# Sheet1.net
KiCad netlist of a schematic drawn in Altium Designer
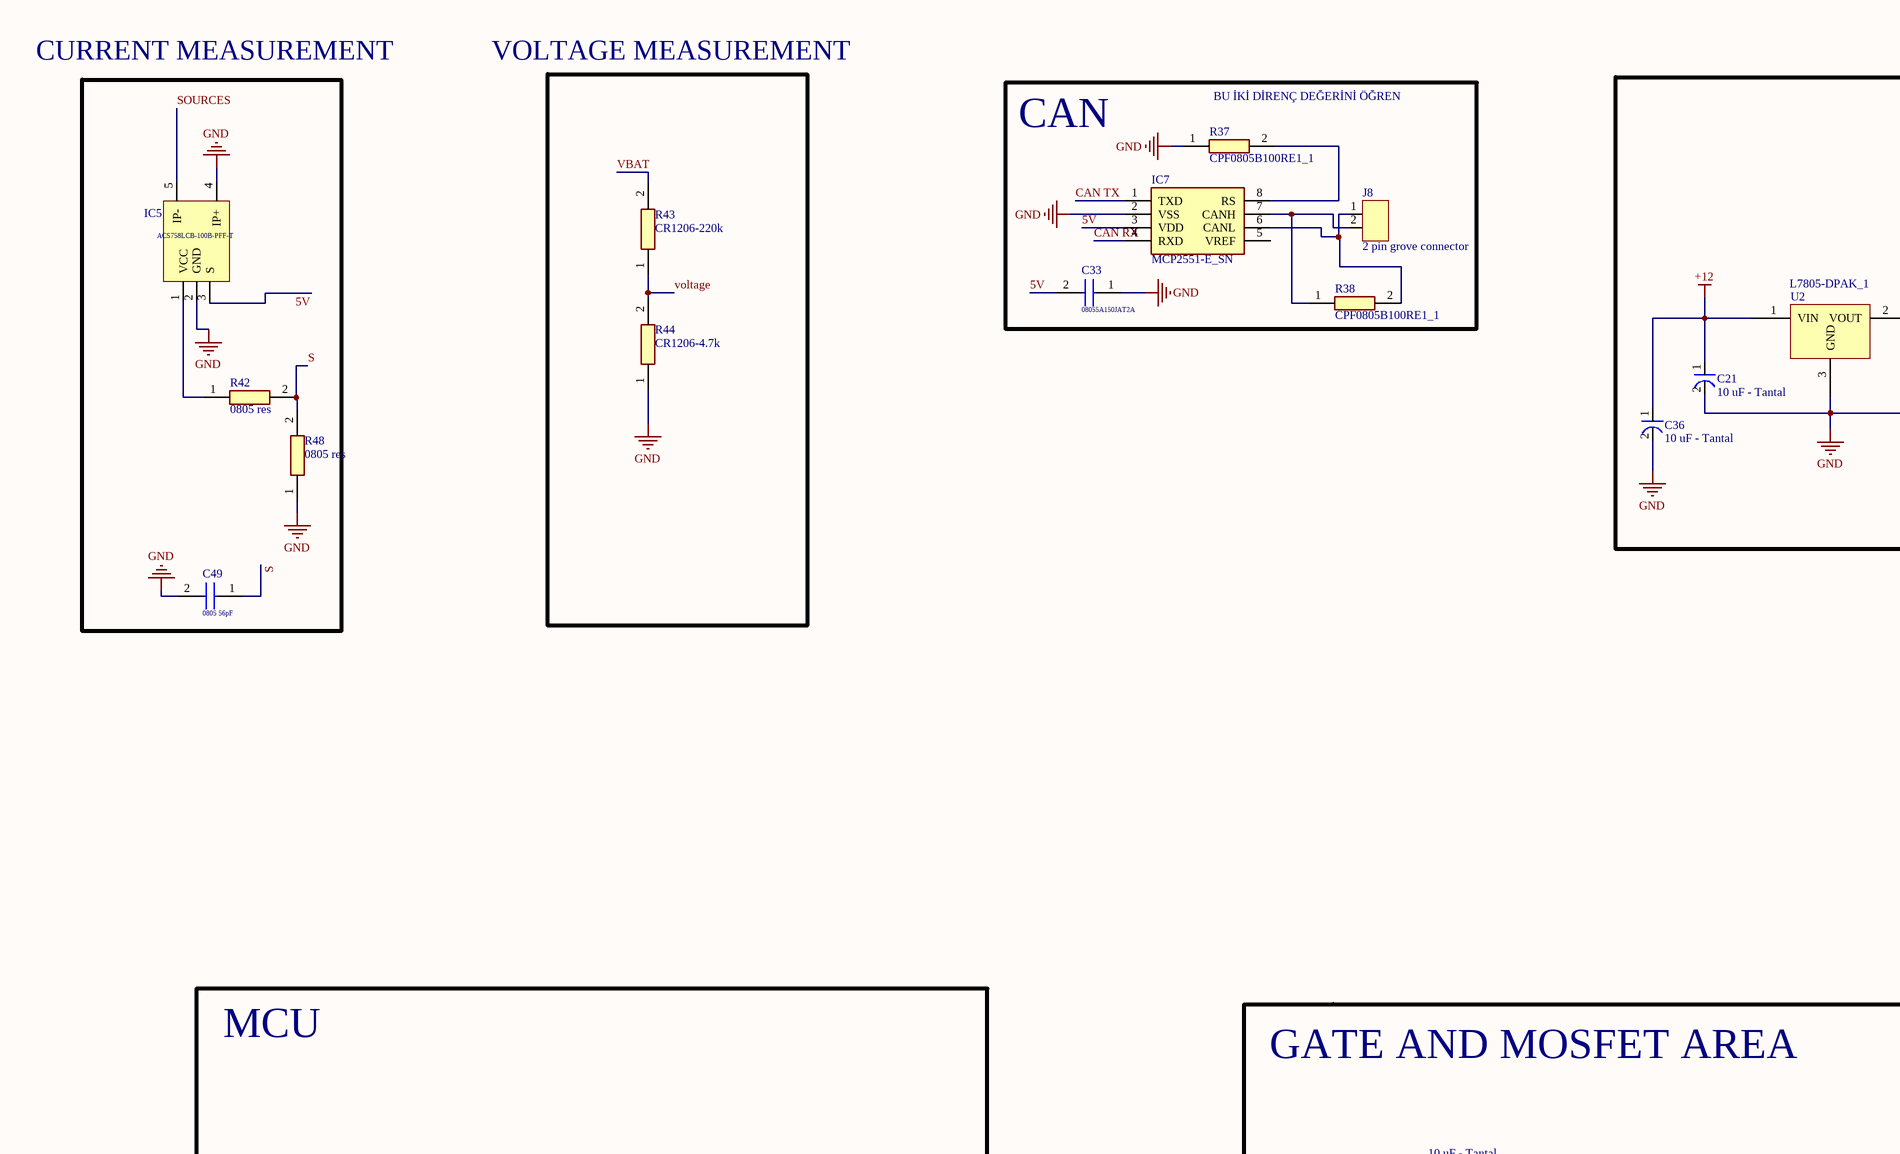
[diagram p0: Sheet1.SchDoc, top left]
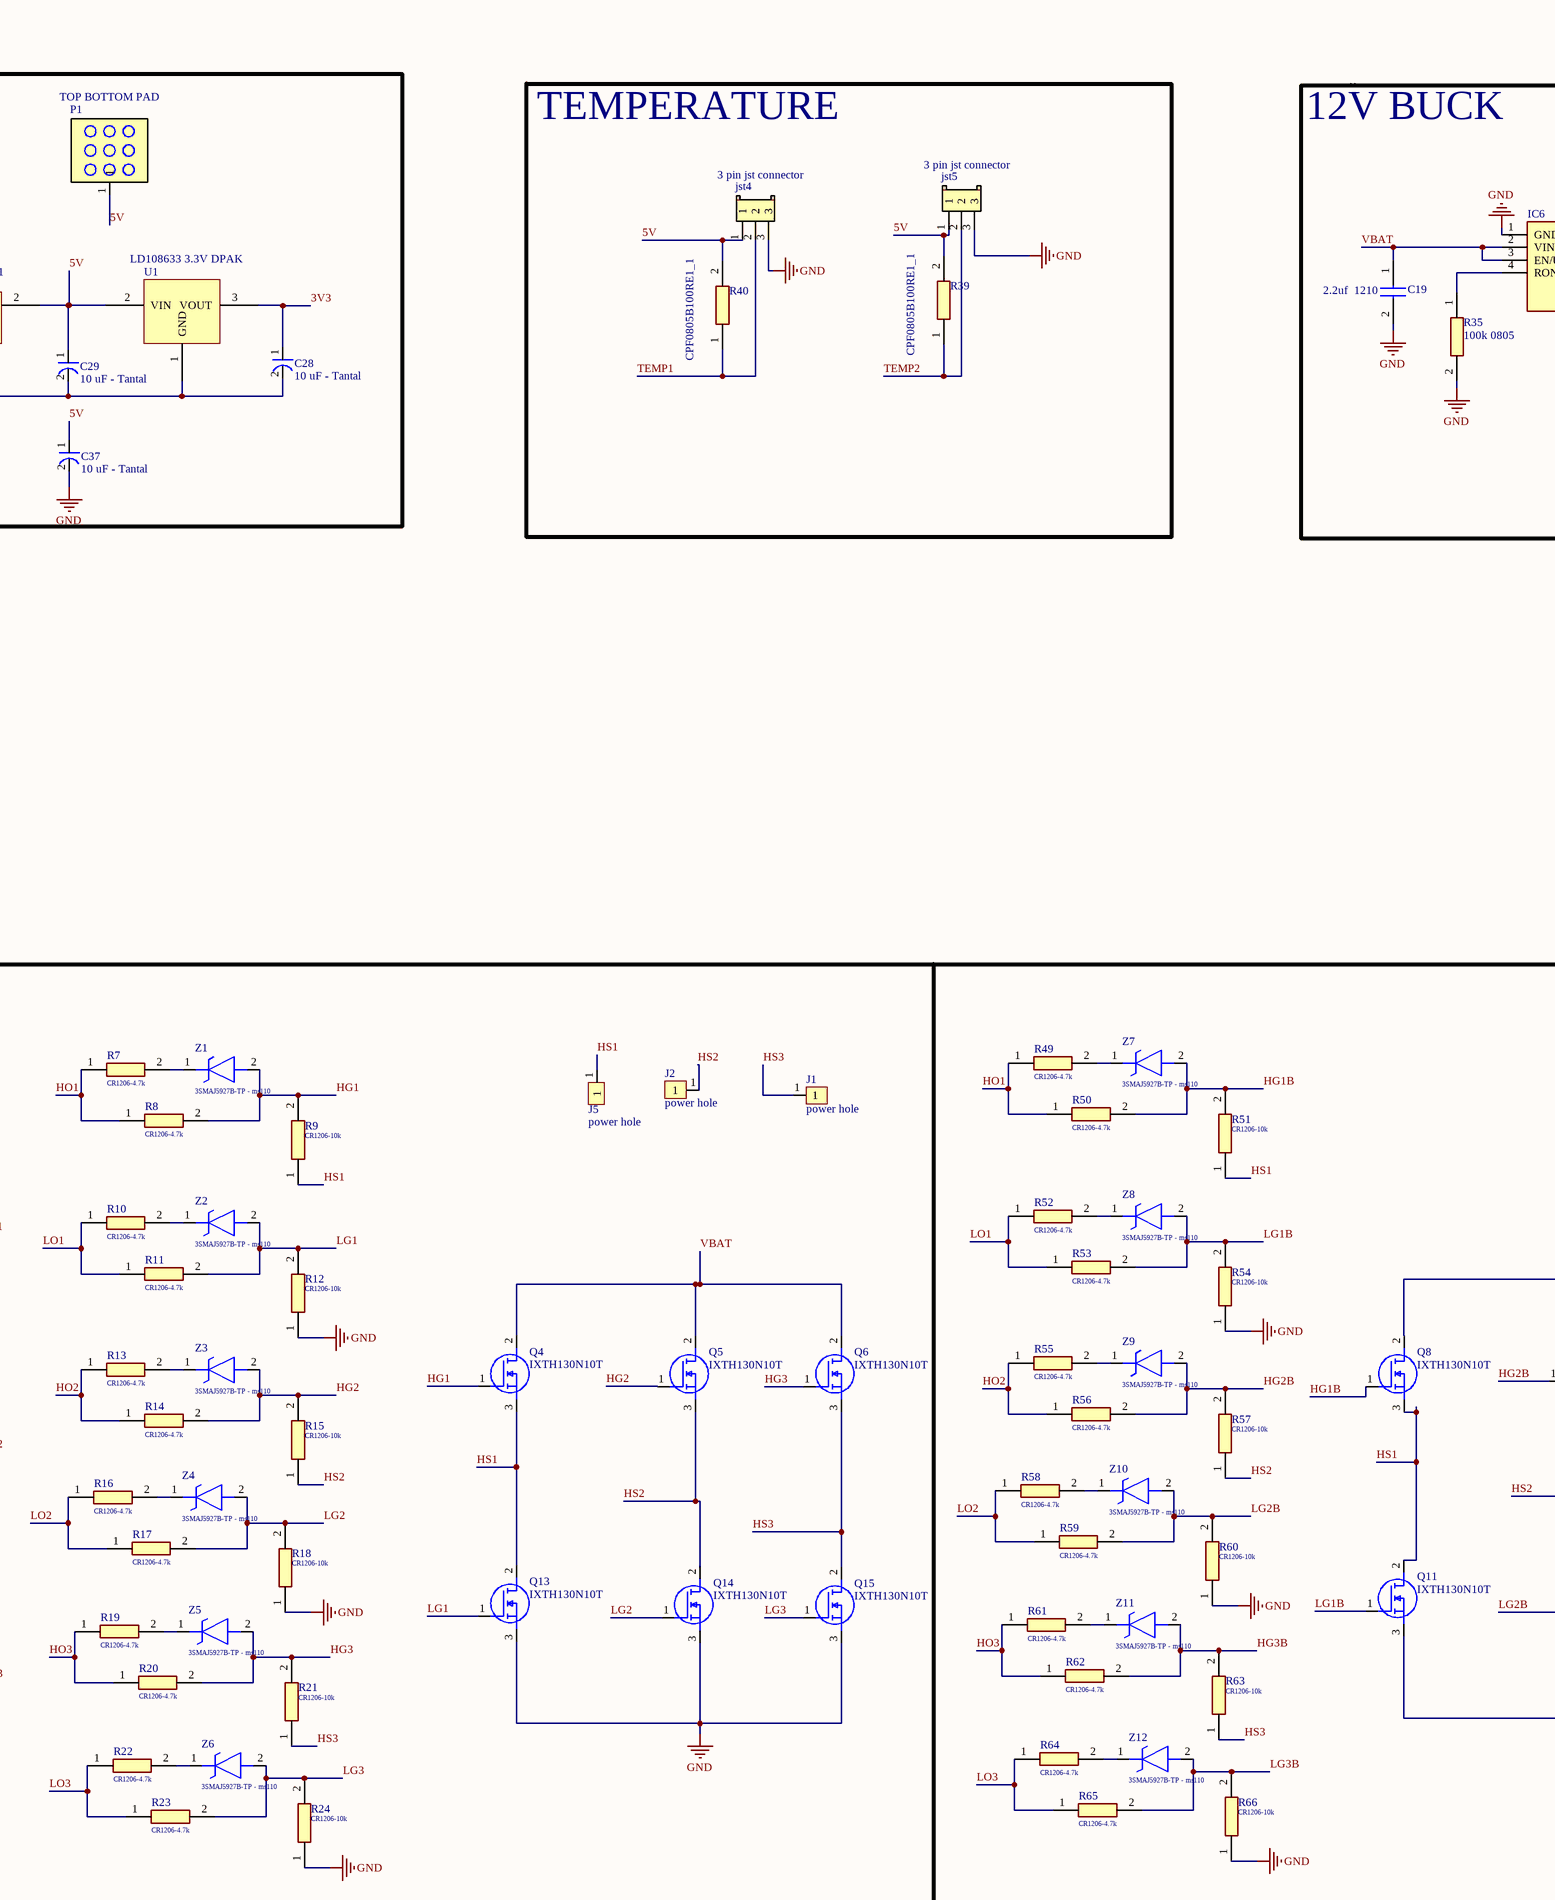
[diagram p1: Sheet1.SchDoc, top middle]
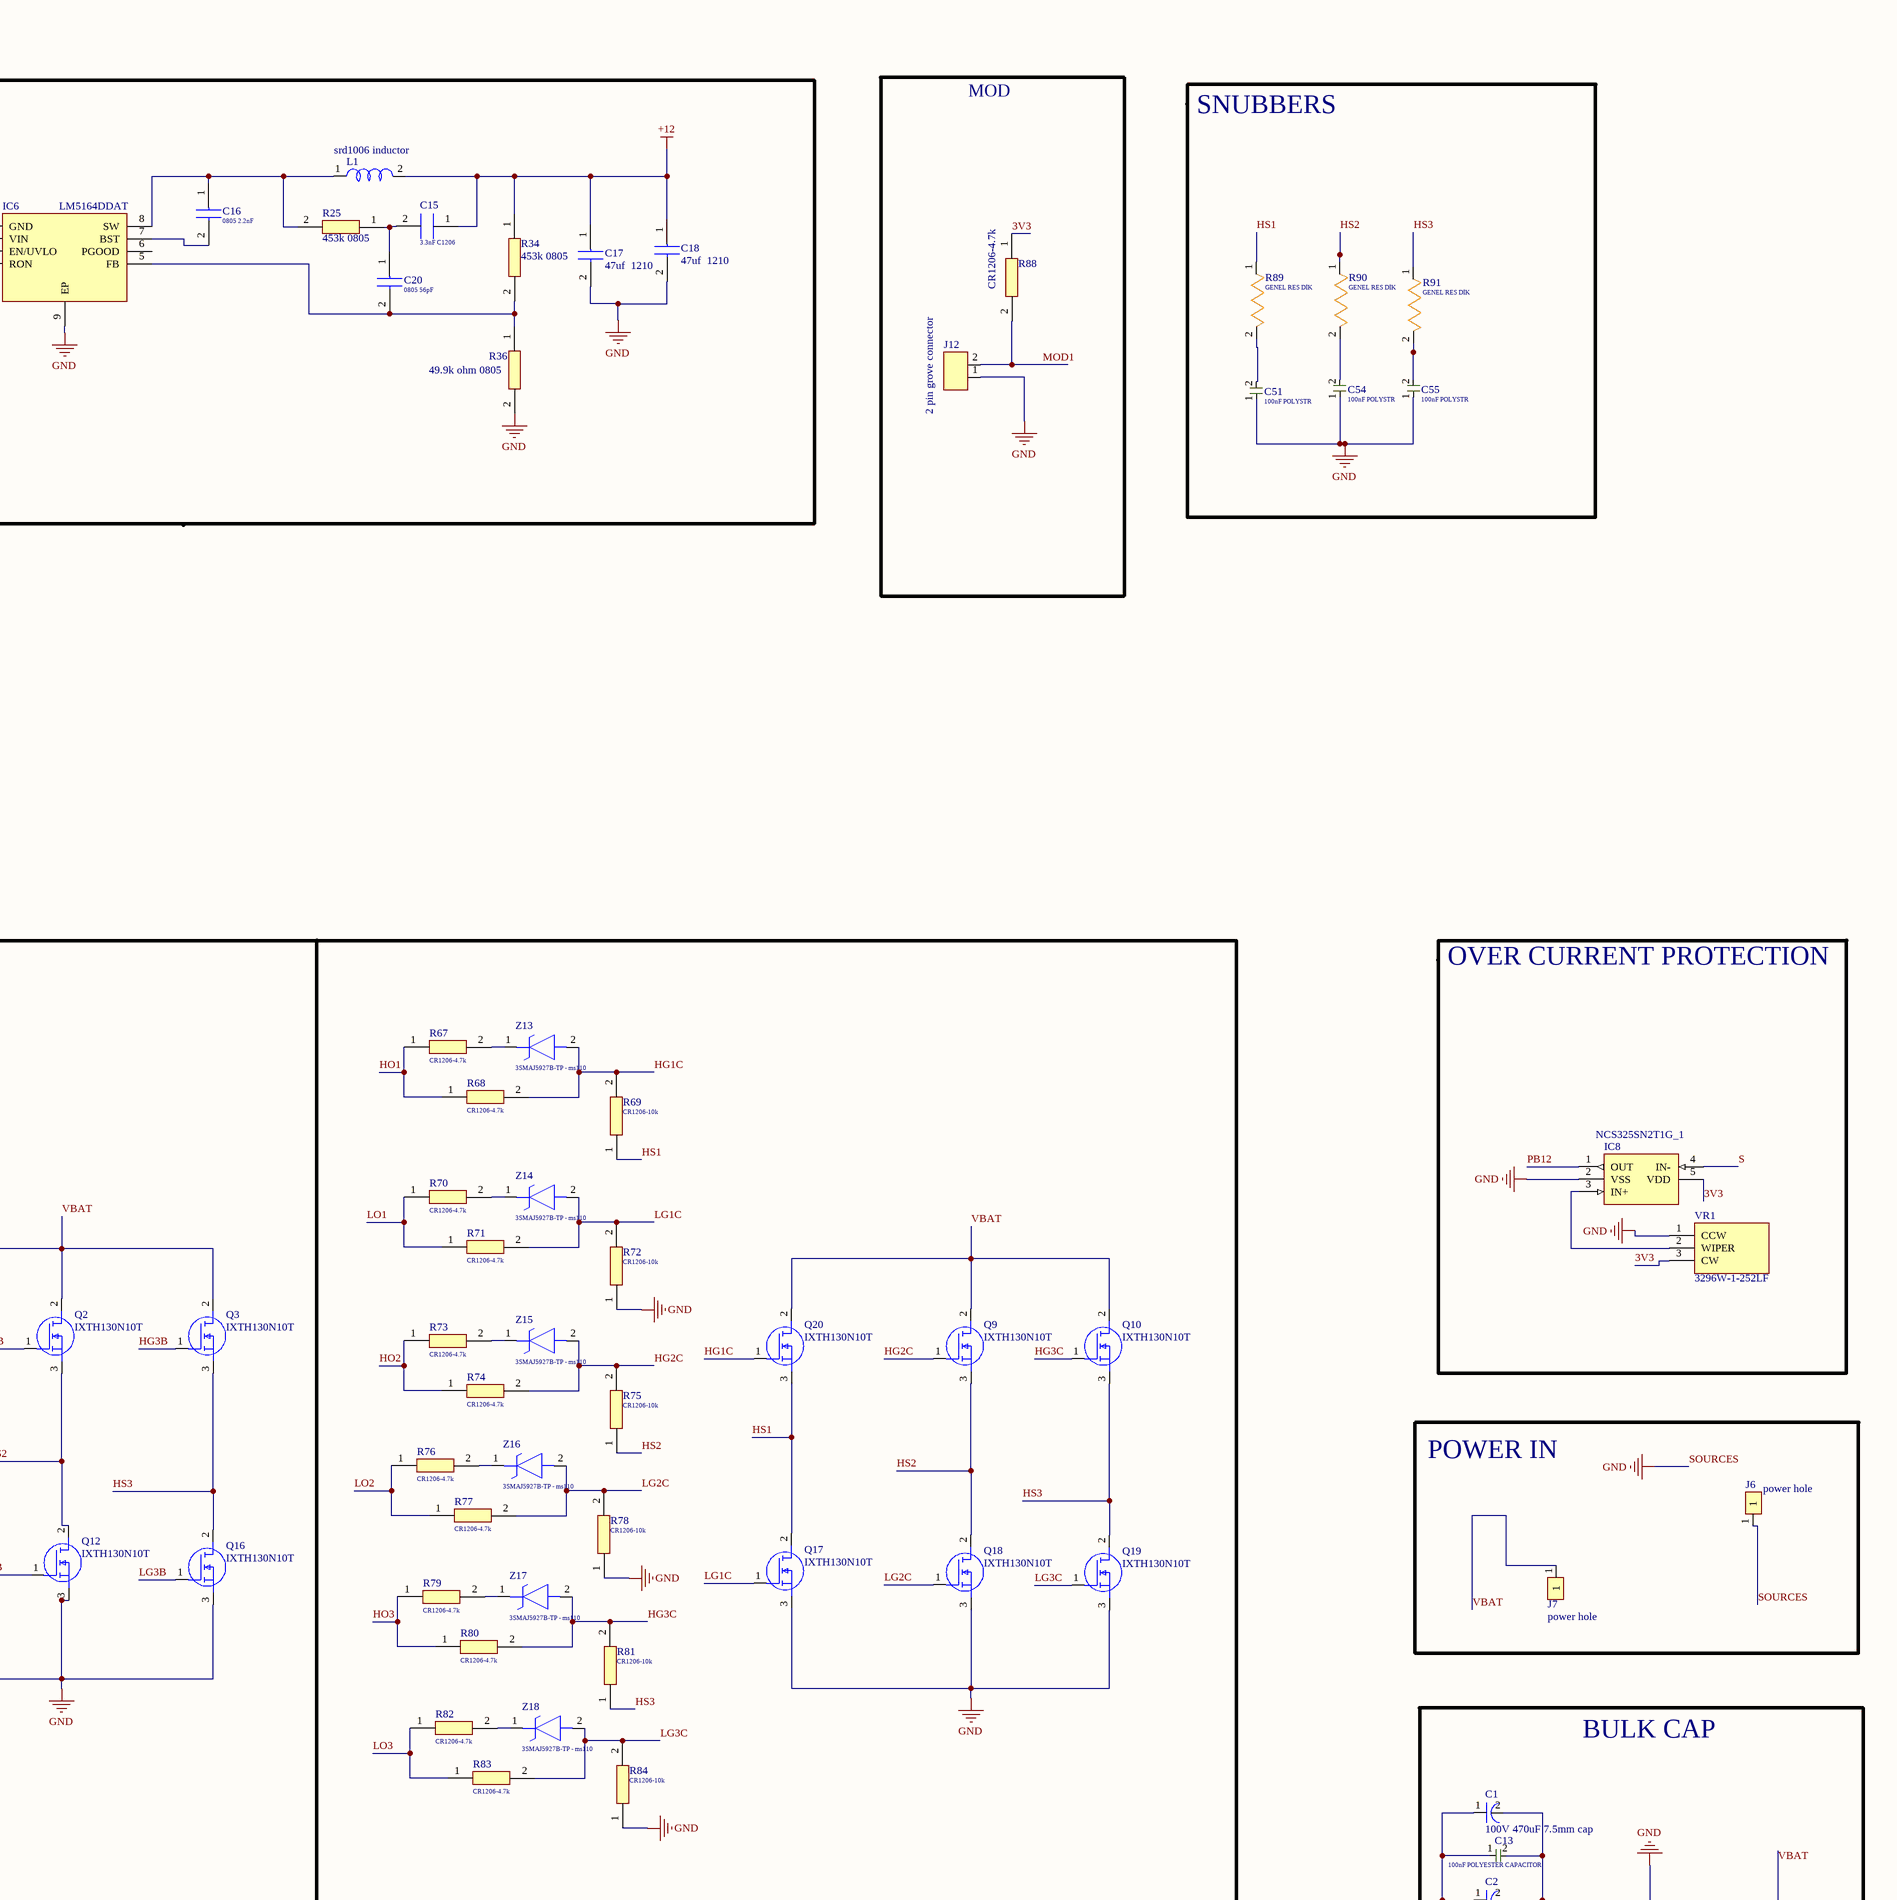
[diagram p2: Sheet1.SchDoc, top right]
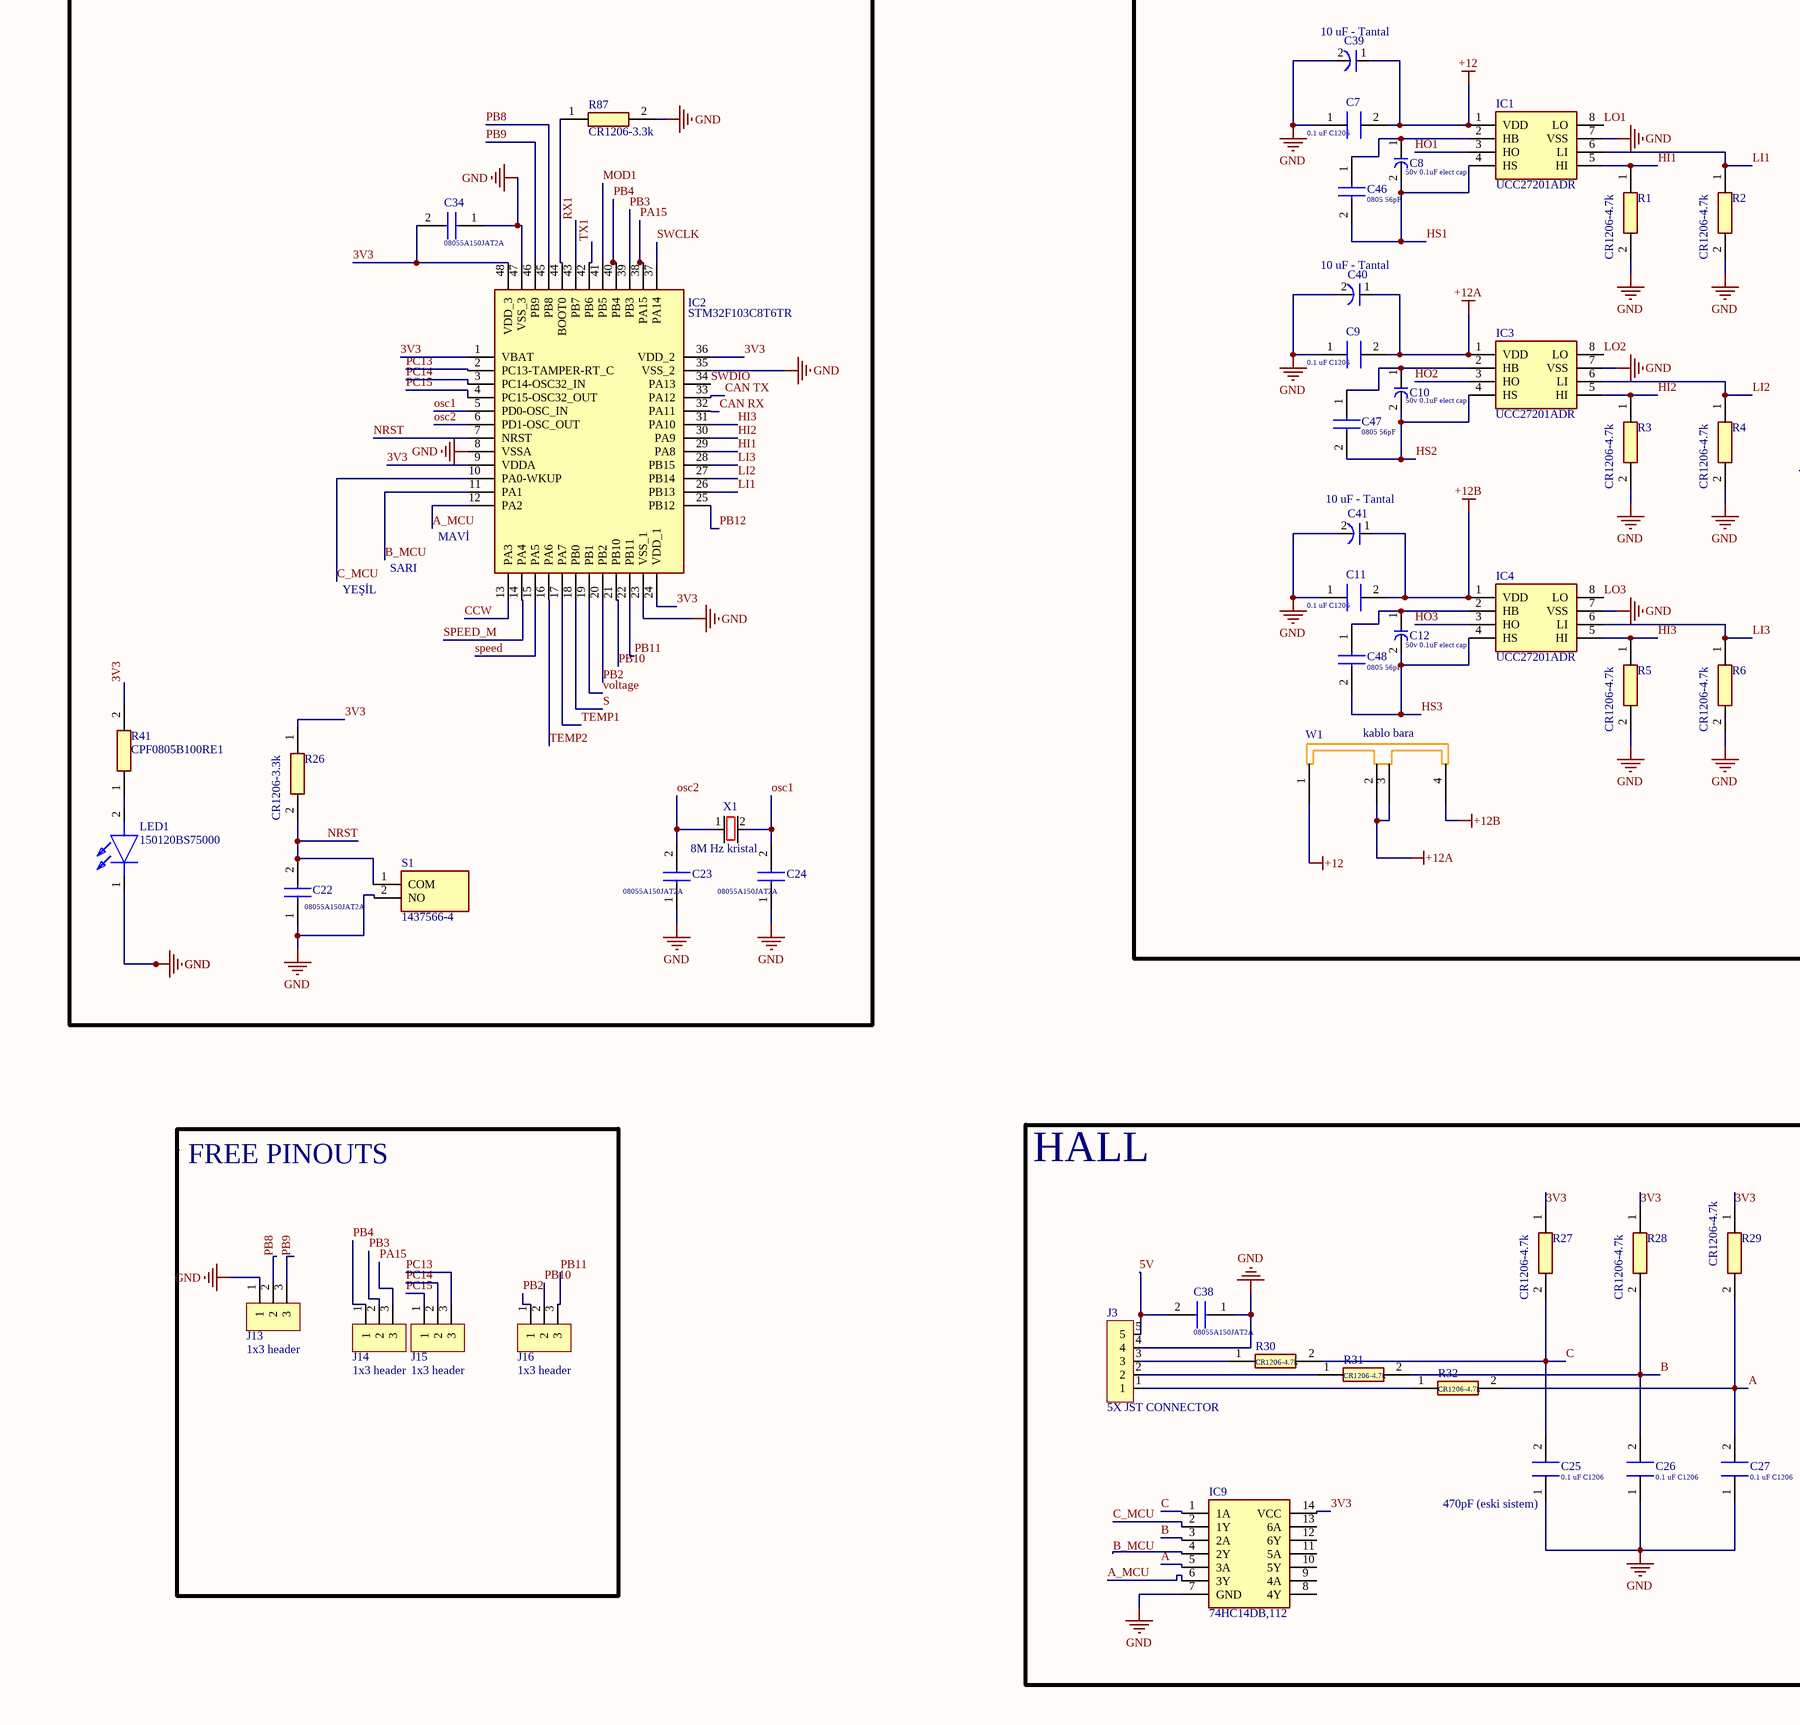
[diagram p3: Sheet1.SchDoc, bottom left]
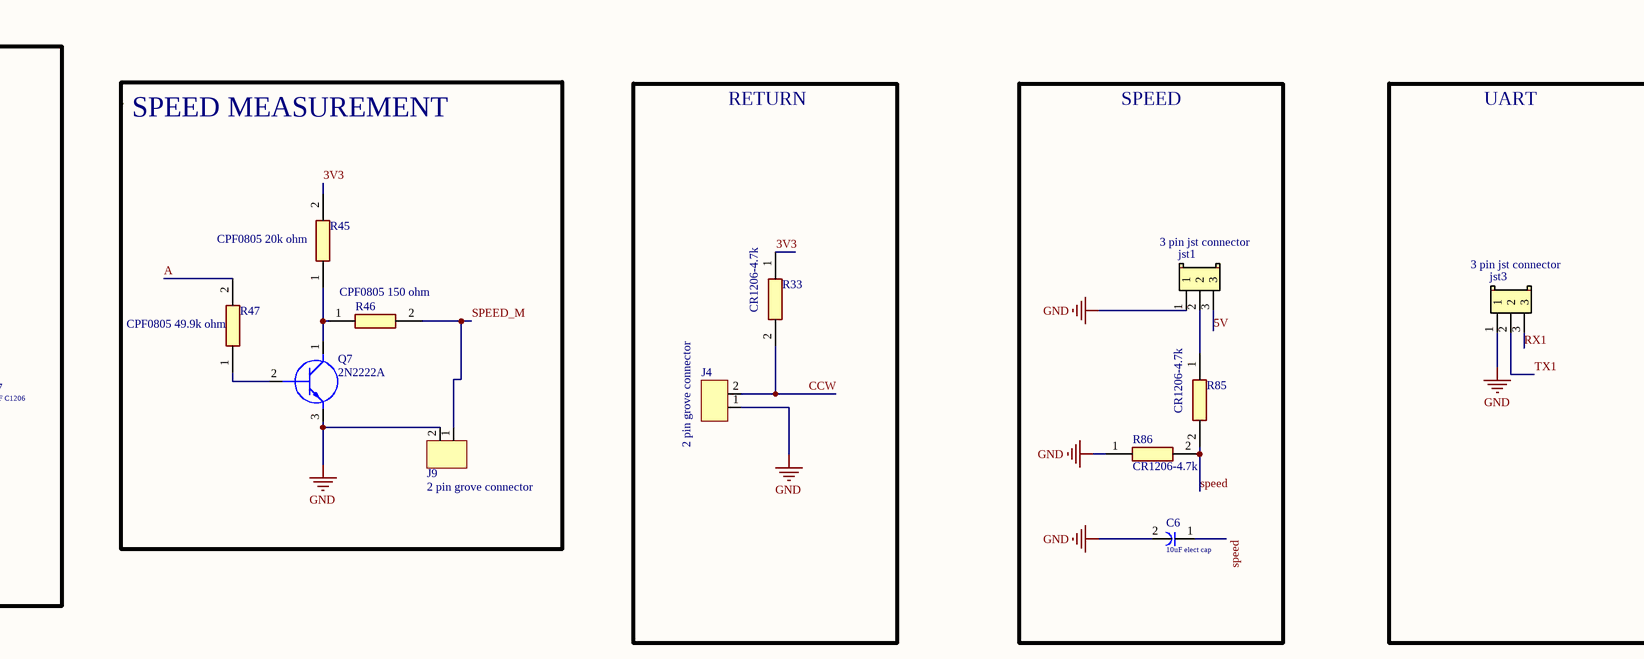
[diagram p4: Sheet1.SchDoc, bottom middle]
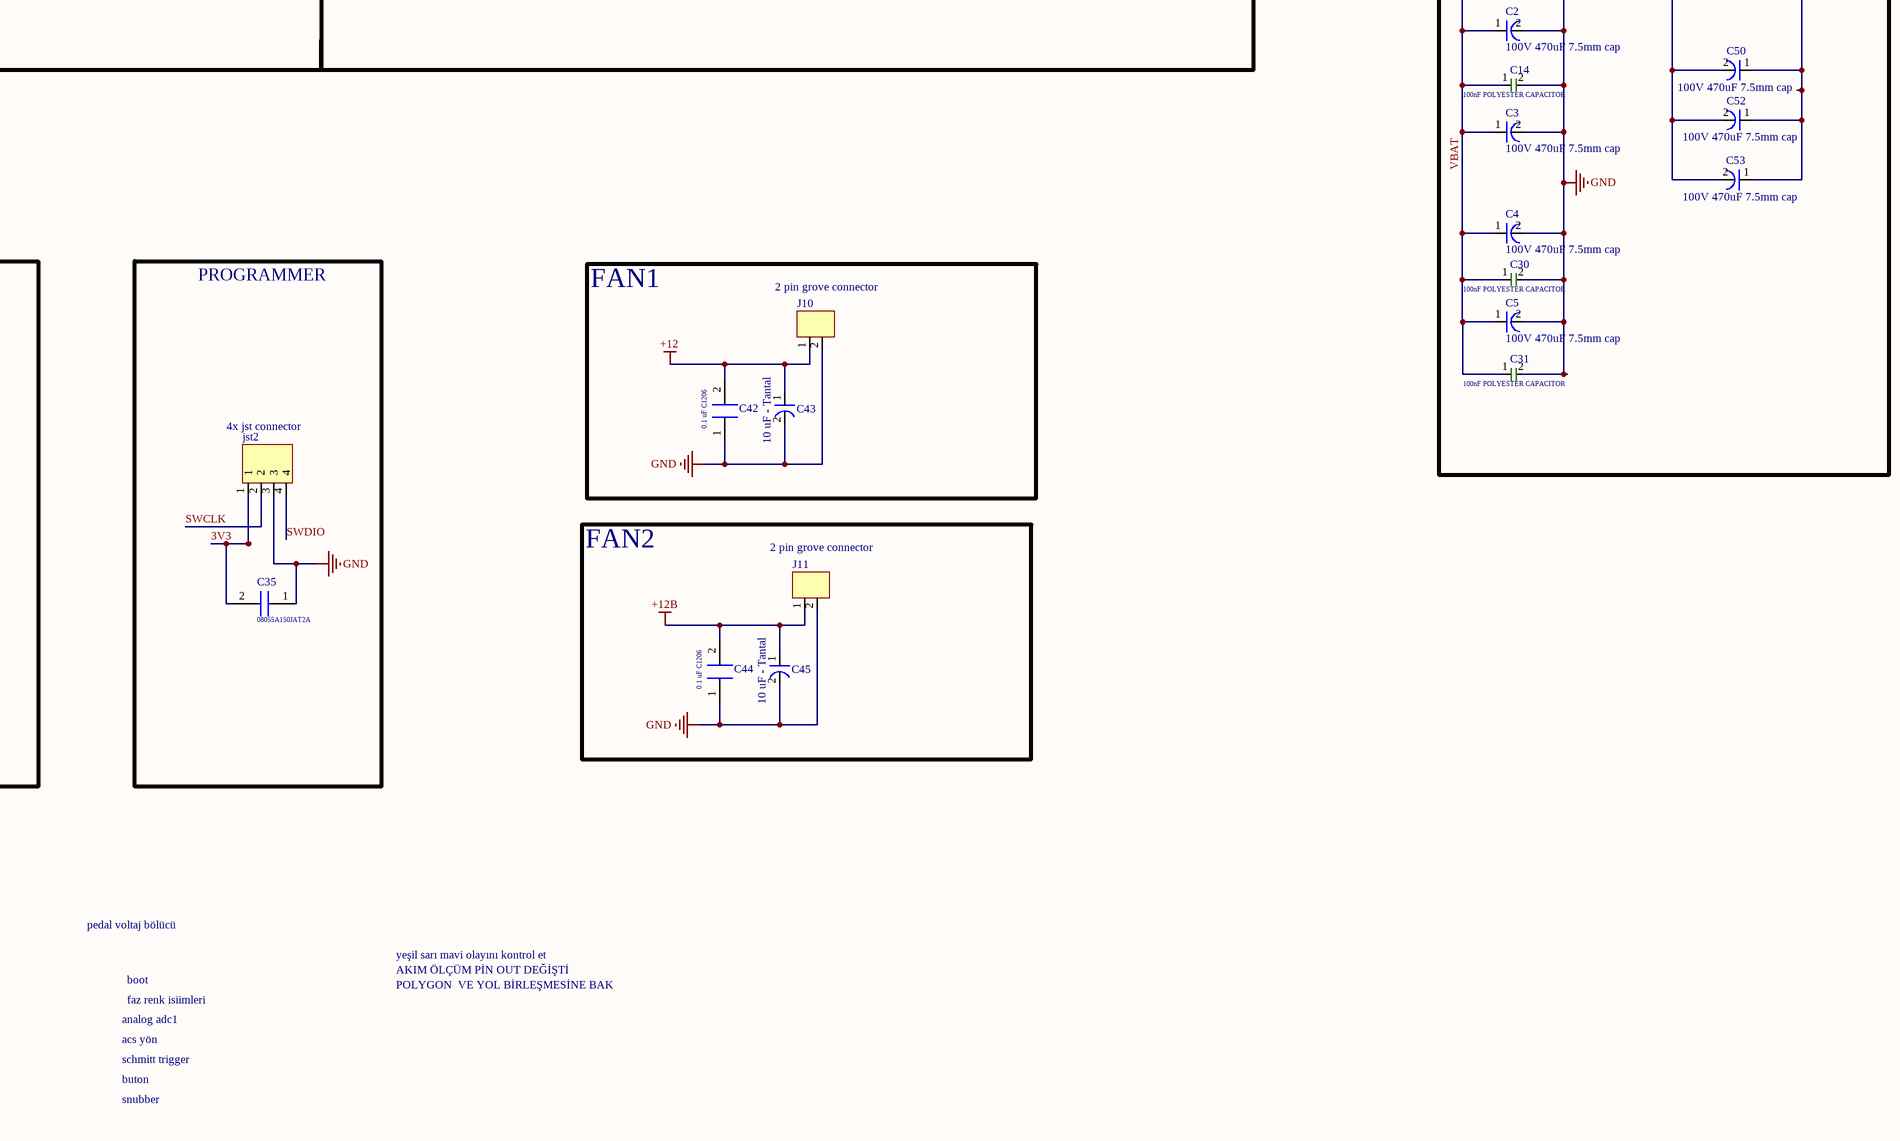
[diagram p5: Sheet1.SchDoc, bottom right]

(export (version "E")
  (design (tool "Eeschema 10.0.6"))
  (components
    (comp (ref "C1")
      (value "100V 470uF 7.5mm cap")
      (footprint "100v 470UF")
      (description "bulk")
      (libsource (lib "Schlib1") (part "100V 470uF 7.5mm cap"))
    )
    (comp (ref "C2")
      (value "100V 470uF 7.5mm cap")
      (footprint "100v 470UF")
      (description "bulk")
      (libsource (lib "Schlib1") (part "100V 470uF 7.5mm cap"))
    )
    (comp (ref "C3")
      (value "100V 470uF 7.5mm cap")
      (footprint "100v 470UF")
      (description "bulk")
      (libsource (lib "Schlib1") (part "100V 470uF 7.5mm cap"))
    )
    (comp (ref "C4")
      (value "100V 470uF 7.5mm cap")
      (footprint "100v 470UF")
      (description "bulk")
      (libsource (lib "Schlib1") (part "100V 470uF 7.5mm cap"))
    )
    (comp (ref "C5")
      (value "100V 470uF 7.5mm cap")
      (footprint "100v 470UF")
      (description "bulk")
      (libsource (lib "Schlib1") (part "100V 470uF 7.5mm cap"))
    )
    (comp (ref "C6")
      (value "10uF elect cap")
      (footprint "50V 0.1uF elect cap")
      (libsource (lib "Schlib1") (part "50v 0.1uF elect cap"))
    )
    (comp (ref "C7")
      (value "0.1 uF C1206")
      (footprint "C1206")
      (libsource (lib "Schlib1") (part "0.1 uF C1206"))
    )
    (comp (ref "C8")
      (value "50v 0.1uF elect cap")
      (footprint "50V 0.1uF elect cap")
      (libsource (lib "Schlib1") (part "50v 0.1uF elect cap"))
    )
    (comp (ref "C9")
      (value "0.1 uF C1206")
      (footprint "C1206")
      (libsource (lib "Schlib1") (part "0.1 uF C1206"))
    )
    (comp (ref "C10")
      (value "50v 0.1uF elect cap")
      (footprint "50V 0.1uF elect cap")
      (libsource (lib "Schlib1") (part "50v 0.1uF elect cap"))
    )
    (comp (ref "C11")
      (value "0.1 uF C1206")
      (footprint "C1206")
      (libsource (lib "Schlib1") (part "0.1 uF C1206"))
    )
    (comp (ref "C12")
      (value "50v 0.1uF elect cap")
      (footprint "50V 0.1uF elect cap")
      (libsource (lib "Schlib1") (part "50v 0.1uF elect cap"))
    )
    (comp (ref "C13")
      (value "100nF POLYESTER CAPACITOR")
      (footprint "100uF POLYESTER CAPACITOR")
      (libsource (lib "Schlib1") (part "100nF POLYESTER CAPACITOR"))
    )
    (comp (ref "C14")
      (value "100nF POLYESTER CAPACITOR")
      (footprint "100uF POLYESTER CAPACITOR")
      (libsource (lib "Schlib1") (part "100nF POLYESTER CAPACITOR"))
    )
    (comp (ref "C15")
      (value "3.3nF C1206")
      (footprint "C1206")
      (description "0.1 uF C1206")
      (libsource (lib "Schlib1") (part "0.1 uF C1206"))
    )
    (comp (ref "C16")
      (value "0805 2.2nF")
      (footprint "PcbLib1:CAPC2012X94N")
      (description "Capacitor")
      (fields
        (field (name "MANUFACTURER_PART_NUMBER") "08055A150JAT2A")
        (field (name "MOUSER PART NUMBER") "581-08055A150J")
      )
      (libsource (lib "Schlib1") (part "08055A150JAT2A"))
    )
    (comp (ref "C17")
      (value "47uf  1210")
      (footprint "PcbLib1:CAPC3225X270N")
      (description "Capacitor")
      (fields
        (field (name "MANUFACTURER_PART_NUMBER") "GRM32EC81C476KE15K")
        (field (name "MOUSER PART NUMBER") "81-GRM32EC81C476KE5K")
      )
      (libsource (lib "*") (part "GRM32EC81C476KE15K"))
    )
    (comp (ref "C18")
      (value "47uf  1210")
      (footprint "PcbLib1:CAPC3225X270N")
      (description "Capacitor")
      (fields
        (field (name "MANUFACTURER_PART_NUMBER") "GRM32EC81C476KE15K")
        (field (name "MOUSER PART NUMBER") "81-GRM32EC81C476KE5K")
      )
      (libsource (lib "*") (part "GRM32EC81C476KE15K"))
    )
    (comp (ref "C19")
      (value "2.2uf  1210")
      (footprint "PcbLib1:CAPC3225X270N")
      (description "Capacitor")
      (fields
        (field (name "MANUFACTURER_PART_NUMBER") "GRM32EC81C476KE15K")
        (field (name "MOUSER PART NUMBER") "81-GRM32EC81C476KE5K")
      )
      (libsource (lib "*") (part "GRM32EC81C476KE15K"))
    )
    (comp (ref "C20")
      (value "0805 56pF")
      (footprint "PcbLib1:CAPC2012X94N")
      (description "Capacitor")
      (fields
        (field (name "MANUFACTURER_PART_NUMBER") "08055A150JAT2A")
        (field (name "MOUSER PART NUMBER") "581-08055A150J")
      )
      (libsource (lib "Schlib1") (part "08055A150JAT2A"))
    )
    (comp (ref "C21")
      (value "10 uF - Tantal")
      (footprint "C1206-TANT")
      (libsource (lib "Schlib1") (part "10 uF - Tantal"))
    )
    (comp (ref "C22")
      (value "08055A150JAT2A")
      (footprint "PcbLib1:CAPC2012X94N")
      (description "Capacitor")
      (fields (field (name "MOUSER PART NUMBER") "581-08055A150J"))
      (libsource (lib "Schlib1") (part "08055A150JAT2A"))
    )
    (comp (ref "C23")
      (value "08055A150JAT2A")
      (footprint "PcbLib1:CAPC2012X94N")
      (description "Capacitor")
      (fields (field (name "MOUSER PART NUMBER") "581-08055A150J"))
      (libsource (lib "Schlib1") (part "08055A150JAT2A"))
    )
    (comp (ref "C24")
      (value "08055A150JAT2A")
      (footprint "PcbLib1:CAPC2012X94N")
      (description "Capacitor")
      (fields (field (name "MOUSER PART NUMBER") "581-08055A150J"))
      (libsource (lib "Schlib1") (part "08055A150JAT2A"))
    )
    (comp (ref "C25")
      (value "0.1 uF C1206")
      (footprint "C1206")
      (libsource (lib "Schlib1") (part "0.1 uF C1206"))
    )
    (comp (ref "C26")
      (value "0.1 uF C1206")
      (footprint "C1206")
      (libsource (lib "Schlib1") (part "0.1 uF C1206"))
    )
    (comp (ref "C27")
      (value "0.1 uF C1206")
      (footprint "C1206")
      (libsource (lib "Schlib1") (part "0.1 uF C1206"))
    )
    (comp (ref "C28")
      (value "10 uF - Tantal")
      (footprint "C1206-TANT")
      (libsource (lib "Schlib1") (part "10 uF - Tantal"))
    )
    (comp (ref "C29")
      (value "10 uF - Tantal")
      (footprint "C1206-TANT")
      (libsource (lib "Schlib1") (part "10 uF - Tantal"))
    )
    (comp (ref "C30")
      (value "100nF POLYESTER CAPACITOR")
      (footprint "100uF POLYESTER CAPACITOR")
      (libsource (lib "Schlib1") (part "100nF POLYESTER CAPACITOR"))
    )
    (comp (ref "C31")
      (value "100nF POLYESTER CAPACITOR")
      (footprint "100uF POLYESTER CAPACITOR")
      (libsource (lib "Schlib1") (part "100nF POLYESTER CAPACITOR"))
    )
    (comp (ref "C33")
      (value "08055A150JAT2A")
      (footprint "PcbLib1:CAPC2012X94N")
      (description "Capacitor")
      (fields (field (name "MOUSER PART NUMBER") "581-08055A150J"))
      (libsource (lib "Schlib1") (part "08055A150JAT2A"))
    )
    (comp (ref "C34")
      (value "08055A150JAT2A")
      (footprint "PcbLib1:CAPC2012X94N")
      (description "Capacitor")
      (fields (field (name "MOUSER PART NUMBER") "581-08055A150J"))
      (libsource (lib "Schlib1") (part "08055A150JAT2A"))
    )
    (comp (ref "C35")
      (value "08055A150JAT2A")
      (footprint "PcbLib1:CAPC2012X94N")
      (description "Capacitor")
      (fields (field (name "MOUSER PART NUMBER") "581-08055A150J"))
      (libsource (lib "Schlib1") (part "08055A150JAT2A"))
    )
    (comp (ref "C36")
      (value "10 uF - Tantal")
      (footprint "C1206-TANT")
      (libsource (lib "Schlib1") (part "10 uF - Tantal"))
    )
    (comp (ref "C37")
      (value "10 uF - Tantal")
      (footprint "C1206-TANT")
      (libsource (lib "Schlib1") (part "10 uF - Tantal"))
    )
    (comp (ref "C38")
      (value "08055A150JAT2A")
      (footprint "PcbLib1:CAPC2012X94N")
      (description "Capacitor")
      (fields (field (name "MOUSER PART NUMBER") "581-08055A150J"))
      (libsource (lib "Schlib1") (part "08055A150JAT2A"))
    )
    (comp (ref "C39")
      (value "10 uF - Tantal")
      (footprint "C1206-TANT")
      (libsource (lib "Schlib1") (part "10 uF - Tantal"))
    )
    (comp (ref "C40")
      (value "10 uF - Tantal")
      (footprint "C1206-TANT")
      (libsource (lib "Schlib1") (part "10 uF - Tantal"))
    )
    (comp (ref "C41")
      (value "10 uF - Tantal")
      (footprint "C1206-TANT")
      (libsource (lib "Schlib1") (part "10 uF - Tantal"))
    )
    (comp (ref "C42")
      (value "0.1 uF C1206")
      (footprint "C1206")
      (libsource (lib "Schlib1") (part "0.1 uF C1206"))
    )
    (comp (ref "C43")
      (value "10 uF - Tantal")
      (footprint "C1206-TANT")
      (libsource (lib "Schlib1") (part "10 uF - Tantal"))
    )
    (comp (ref "C44")
      (value "0.1 uF C1206")
      (footprint "C1206")
      (libsource (lib "Schlib1") (part "0.1 uF C1206"))
    )
    (comp (ref "C45")
      (value "10 uF - Tantal")
      (footprint "C1206-TANT")
      (libsource (lib "Schlib1") (part "10 uF - Tantal"))
    )
    (comp (ref "C46")
      (value "0805 56pF")
      (footprint "PcbLib1:CAPC2012X94N")
      (description "Capacitor")
      (fields
        (field (name "MANUFACTURER_PART_NUMBER") "08055A150JAT2A")
        (field (name "MOUSER PART NUMBER") "581-08055A150J")
      )
      (libsource (lib "Schlib1") (part "08055A150JAT2A"))
    )
    (comp (ref "C47")
      (value "0805 56pF")
      (footprint "PcbLib1:CAPC2012X94N")
      (description "Capacitor")
      (fields
        (field (name "MANUFACTURER_PART_NUMBER") "08055A150JAT2A")
        (field (name "MOUSER PART NUMBER") "581-08055A150J")
      )
      (libsource (lib "Schlib1") (part "08055A150JAT2A"))
    )
    (comp (ref "C48")
      (value "0805 56pF")
      (footprint "PcbLib1:CAPC2012X94N")
      (description "Capacitor")
      (fields
        (field (name "MANUFACTURER_PART_NUMBER") "08055A150JAT2A")
        (field (name "MOUSER PART NUMBER") "581-08055A150J")
      )
      (libsource (lib "Schlib1") (part "08055A150JAT2A"))
    )
    (comp (ref "C49")
      (value "0805 56pF")
      (footprint "PcbLib1:CAPC2012X94N")
      (description "Capacitor")
      (fields
        (field (name "MANUFACTURER_PART_NUMBER") "08055A150JAT2A")
        (field (name "MOUSER PART NUMBER") "581-08055A150J")
      )
      (libsource (lib "Schlib1") (part "08055A150JAT2A"))
    )
    (comp (ref "C50")
      (value "100V 470uF 7.5mm cap")
      (footprint "100v 470UF")
      (description "bulk")
      (libsource (lib "Schlib1") (part "100V 470uF 7.5mm cap"))
    )
    (comp (ref "C51")
      (value "100nF POLYSTR")
      (footprint "100uF POLYESTER CAPACITOR")
      (libsource (lib "Schlib1") (part "100nF POLYESTER CAPACITOR"))
    )
    (comp (ref "C52")
      (value "100V 470uF 7.5mm cap")
      (footprint "100v 470UF")
      (description "bulk")
      (libsource (lib "Schlib1") (part "100V 470uF 7.5mm cap"))
    )
    (comp (ref "C53")
      (value "100V 470uF 7.5mm cap")
      (footprint "100v 470UF")
      (description "bulk")
      (libsource (lib "Schlib1") (part "100V 470uF 7.5mm cap"))
    )
    (comp (ref "C54")
      (value "100nF POLYSTR")
      (footprint "100uF POLYESTER CAPACITOR")
      (libsource (lib "Schlib1") (part "100nF POLYESTER CAPACITOR"))
    )
    (comp (ref "C55")
      (value "100nF POLYSTR")
      (footprint "100uF POLYESTER CAPACITOR")
      (libsource (lib "Schlib1") (part "100nF POLYESTER CAPACITOR"))
    )
    (comp (ref "IC1")
      (value "UCC27201ADR")
      (footprint "SOIC127P600X175-8N")
      (description "Integrated Circuit")
      (fields (field (name "MOUSER PART NUMBER") "595-UCC27201ADR"))
      (libsource (lib "Schlib1") (part "UCC27201ADR"))
    )
    (comp (ref "IC2")
      (value "STM32F103C8T6TR")
      (footprint "PcbLib1:QFP50P900X900X160-48N")
      (description "Integrated Circuit")
      (fields (field (name "MOUSER PART NUMBER") "511-STM32F103C8T6TR"))
      (libsource (lib "*") (part "STM32F103C8T6TR"))
    )
    (comp (ref "IC3")
      (value "UCC27201ADR")
      (footprint "SOIC127P600X175-8N")
      (description "Integrated Circuit")
      (fields (field (name "MOUSER PART NUMBER") "595-UCC27201ADR"))
      (libsource (lib "Schlib1") (part "UCC27201ADR"))
    )
    (comp (ref "IC4")
      (value "UCC27201ADR")
      (footprint "SOIC127P600X175-8N")
      (description "Integrated Circuit")
      (fields (field (name "MOUSER PART NUMBER") "595-UCC27201ADR"))
      (libsource (lib "Schlib1") (part "UCC27201ADR"))
    )
    (comp (ref "IC5")
      (value "ACS758LCB-100B-PFF-T")
      (footprint "ACS772ECB200BPFFT")
      (description "Integrated Circuit")
      (fields (field (name "MOUSER PART NUMBER") "250-758LCB100BPFFT"))
      (libsource (lib "Schlib1") (part "ACS758LCB-100B-PFF-T"))
    )
    (comp (ref "IC6")
      (value "LM5164DDAT")
      (footprint "PcbLib1:SOIC127P600X170-9N")
      (description "Integrated Circuit")
      (fields (field (name "MOUSER PART NUMBER") "595-LM5164DDAT"))
      (libsource (lib "*") (part "LM5164DDAT"))
    )
    (comp (ref "IC7")
      (value "MCP2551-E_SN")
      (footprint "PcbLib1:SOIC127P600X175-8N")
      (description "Integrated Circuit")
      (fields
        (field (name "MANUFACTURER_PART_NUMBER") "MCP2551-E/SN")
        (field (name "MOUSER PART NUMBER") "579-MCP2551-E/SN")
      )
      (libsource (lib "Schlib1") (part "MCP2551-E_SN"))
    )
    (comp (ref "IC8")
      (value "NCS325SN2T1G_1")
      (footprint "SOT95P275X110-5N")
      (description "Integrated Circuit")
      (fields
        (field (name "MANUFACTURER_PART_NUMBER") "NCS325SN2T1G")
        (field (name "MOUSER PART NUMBER") "863-NCS325SN2T1G")
      )
      (libsource (lib "Schlib1") (part "NCS325SN2T1G_1"))
    )
    (comp (ref "IC9")
      (value "74HC14DB,112")
      (footprint "PcbLib1:SOIC127P600X175-14N")
      (description "Integrated Circuit")
      (fields (field (name "MOUSER PART NUMBER") "771-74HC14DB"))
      (libsource (lib "Schlib1") (part "74HC14DB,112"))
    )
    (comp (ref "J1")
      (value "power hole")
      (footprint "power hole metric5")
      (libsource (lib "") (part "power hole_3"))
    )
    (comp (ref "J2")
      (value "power hole")
      (footprint "power hole metric5")
      (libsource (lib "Schlib1") (part "power hole"))
    )
    (comp (ref "J3")
      (value "5X JST CONNECTOR")
      (footprint "5X HEADER")
      (libsource (lib "Schlib1") (part "5X HEADER"))
    )
    (comp (ref "J4")
      (value "2 pin grove connector")
      (footprint "2 pin grove connector")
      (libsource (lib "") (part "2 pin grove connector_1"))
    )
    (comp (ref "J5")
      (value "power hole")
      (footprint "power hole metric5")
      (libsource (lib "") (part "power hole_1"))
    )
    (comp (ref "J6")
      (value "power hole")
      (footprint "power hole metric5")
      (libsource (lib "") (part "power hole_2"))
    )
    (comp (ref "J7")
      (value "power hole")
      (footprint "power hole metric5")
      (libsource (lib "") (part "power hole_1"))
    )
    (comp (ref "J8")
      (value "2 pin grove connector")
      (footprint "2 pin grove connector")
      (libsource (lib "") (part "2 pin grove connector_3"))
    )
    (comp (ref "J9")
      (value "2 pin grove connector")
      (footprint "2 pin grove connector")
      (libsource (lib "Schlib1") (part "2 pin grove connector"))
    )
    (comp (ref "J10")
      (value "2 pin grove connector")
      (footprint "2 pin grove connector")
      (libsource (lib "") (part "2 pin grove connector_2"))
    )
    (comp (ref "J11")
      (value "2 pin grove connector")
      (footprint "2 pin grove connector")
      (libsource (lib "") (part "2 pin grove connector_2"))
    )
    (comp (ref "J12")
      (value "2 pin grove connector")
      (footprint "2 pin grove connector")
      (libsource (lib "") (part "2 pin grove connector_1"))
    )
    (comp (ref "J13")
      (value "1x3 header")
      (footprint "1x3 header")
      (libsource (lib "Schlib1") (part "1x3 header"))
    )
    (comp (ref "J14")
      (value "1x3 header")
      (footprint "1x3 header")
      (libsource (lib "Schlib1") (part "1x3 header"))
    )
    (comp (ref "J15")
      (value "1x3 header")
      (footprint "1x3 header")
      (libsource (lib "Schlib1") (part "1x3 header"))
    )
    (comp (ref "J16")
      (value "1x3 header")
      (footprint "1x3 header")
      (libsource (lib "Schlib1") (part "1x3 header"))
    )
    (comp (ref "jst1")
      (value "3 pin jst connector")
      (footprint "3 pin jst connector")
      (libsource (lib "Schlib1") (part "3 pin jst connector"))
    )
    (comp (ref "jst2")
      (value "4x jst connector")
      (footprint "4x jst connector")
      (libsource (lib "Schlib1") (part "4x jst connector"))
    )
    (comp (ref "jst3")
      (value "3 pin jst connector")
      (footprint "3 pin jst connector")
      (libsource (lib "Schlib1") (part "3 pin jst connector"))
    )
    (comp (ref "jst4")
      (value "3 pin jst connector")
      (footprint "3 pin jst connector")
      (libsource (lib "Schlib1") (part "3 pin jst connector"))
    )
    (comp (ref "jst5")
      (value "3 pin jst connector")
      (footprint "3 pin jst connector")
      (libsource (lib "Schlib1") (part "3 pin jst connector"))
    )
    (comp (ref "L1")
      (value "srd1006 inductor")
      (footprint "srd1006")
      (description "inductor")
      (libsource (lib "Schlib1") (part "srd1006 inductor"))
    )
    (comp (ref "LED1")
      (value "150120BS75000")
      (footprint "PcbLib1:LEDC3214X78N")
      (description "LED")
      (fields (field (name "MOUSER PART NUMBER") "710-150120BS75000"))
      (libsource (lib "Schlib1") (part "150120BS75000"))
    )
    (comp (ref "P1")
      (value "TOP BOTTOM PAD")
      (footprint "TOP BOTTOM PAD")
      (description "PAD")
      (libsource (lib "Schlib1") (part "TOP BOTTOM PAD"))
    )
    (comp (ref "Q2")
      (value "IXTH130N10T")
      (footprint "IXTH130N10T")
      (description "n-channel mosfet")
      (libsource (lib "Schlib1") (part "IXTH130N10T"))
    )
    (comp (ref "Q3")
      (value "IXTH130N10T")
      (footprint "IXTH130N10T")
      (description "n-channel mosfet")
      (libsource (lib "Schlib1") (part "IXTH130N10T"))
    )
    (comp (ref "Q4")
      (value "IXTH130N10T")
      (footprint "IXTH130N10T")
      (description "n-channel mosfet")
      (libsource (lib "Schlib1") (part "IXTH130N10T"))
    )
    (comp (ref "Q5")
      (value "IXTH130N10T")
      (footprint "IXTH130N10T")
      (description "n-channel mosfet")
      (libsource (lib "Schlib1") (part "IXTH130N10T"))
    )
    (comp (ref "Q6")
      (value "IXTH130N10T")
      (footprint "IXTH130N10T")
      (description "n-channel mosfet")
      (libsource (lib "Schlib1") (part "IXTH130N10T"))
    )
    (comp (ref "Q7")
      (value "2N2222A")
      (footprint "PcbLib1:2N2222A")
      (description "Transistor BJT NPN")
      (libsource (lib "Schlib1") (part "2N2222A"))
    )
    (comp (ref "Q8")
      (value "IXTH130N10T")
      (footprint "IXTH130N10T")
      (description "n-channel mosfet")
      (libsource (lib "Schlib1") (part "IXTH130N10T"))
    )
    (comp (ref "Q9")
      (value "IXTH130N10T")
      (footprint "IXTH130N10T")
      (description "n-channel mosfet")
      (libsource (lib "Schlib1") (part "IXTH130N10T"))
    )
    (comp (ref "Q10")
      (value "IXTH130N10T")
      (footprint "IXTH130N10T")
      (description "n-channel mosfet")
      (libsource (lib "Schlib1") (part "IXTH130N10T"))
    )
    (comp (ref "Q11")
      (value "IXTH130N10T")
      (footprint "IXTH130N10T")
      (description "n-channel mosfet")
      (libsource (lib "Schlib1") (part "IXTH130N10T"))
    )
    (comp (ref "Q12")
      (value "IXTH130N10T")
      (footprint "IXTH130N10T")
      (description "n-channel mosfet")
      (libsource (lib "Schlib1") (part "IXTH130N10T"))
    )
    (comp (ref "Q13")
      (value "IXTH130N10T")
      (footprint "IXTH130N10T")
      (description "n-channel mosfet")
      (libsource (lib "Schlib1") (part "IXTH130N10T"))
    )
    (comp (ref "Q14")
      (value "IXTH130N10T")
      (footprint "IXTH130N10T")
      (description "n-channel mosfet")
      (libsource (lib "Schlib1") (part "IXTH130N10T"))
    )
    (comp (ref "Q15")
      (value "IXTH130N10T")
      (footprint "IXTH130N10T")
      (description "n-channel mosfet")
      (libsource (lib "Schlib1") (part "IXTH130N10T"))
    )
    (comp (ref "Q16")
      (value "IXTH130N10T")
      (footprint "IXTH130N10T")
      (description "n-channel mosfet")
      (libsource (lib "Schlib1") (part "IXTH130N10T"))
    )
    (comp (ref "Q17")
      (value "IXTH130N10T")
      (footprint "IXTH130N10T")
      (description "n-channel mosfet")
      (libsource (lib "Schlib1") (part "IXTH130N10T"))
    )
    (comp (ref "Q18")
      (value "IXTH130N10T")
      (footprint "IXTH130N10T")
      (description "n-channel mosfet")
      (libsource (lib "Schlib1") (part "IXTH130N10T"))
    )
    (comp (ref "Q19")
      (value "IXTH130N10T")
      (footprint "IXTH130N10T")
      (description "n-channel mosfet")
      (libsource (lib "Schlib1") (part "IXTH130N10T"))
    )
    (comp (ref "Q20")
      (value "IXTH130N10T")
      (footprint "IXTH130N10T")
      (description "n-channel mosfet")
      (libsource (lib "Schlib1") (part "IXTH130N10T"))
    )
    (comp (ref "R1")
      (value "CR1206-4.7k")
      (footprint "PcbLib1:RESC3216X75N")
      (description "Resistor")
      (fields
        (field (name "MANUFACTURER_PART_NUMBER") "CR1206-F/-2R70ELF")
        (field (name "MOUSER PART NUMBER") "652-CR1206-F/2R70ELF")
      )
      (libsource (lib "") (part "CR1206-F_-2R70ELF_2"))
    )
    (comp (ref "R2")
      (value "CR1206-4.7k")
      (footprint "PcbLib1:RESC3216X75N")
      (description "Resistor")
      (fields
        (field (name "MANUFACTURER_PART_NUMBER") "CR1206-F/-2R70ELF")
        (field (name "MOUSER PART NUMBER") "652-CR1206-F/2R70ELF")
      )
      (libsource (lib "") (part "CR1206-F_-2R70ELF_2"))
    )
    (comp (ref "R3")
      (value "CR1206-4.7k")
      (footprint "PcbLib1:RESC3216X75N")
      (description "Resistor")
      (fields
        (field (name "MANUFACTURER_PART_NUMBER") "CR1206-F/-2R70ELF")
        (field (name "MOUSER PART NUMBER") "652-CR1206-F/2R70ELF")
      )
      (libsource (lib "") (part "CR1206-F_-2R70ELF_2"))
    )
    (comp (ref "R4")
      (value "CR1206-4.7k")
      (footprint "PcbLib1:RESC3216X75N")
      (description "Resistor")
      (fields
        (field (name "MANUFACTURER_PART_NUMBER") "CR1206-F/-2R70ELF")
        (field (name "MOUSER PART NUMBER") "652-CR1206-F/2R70ELF")
      )
      (libsource (lib "") (part "CR1206-F_-2R70ELF_2"))
    )
    (comp (ref "R5")
      (value "CR1206-4.7k")
      (footprint "PcbLib1:RESC3216X75N")
      (description "Resistor")
      (fields
        (field (name "MANUFACTURER_PART_NUMBER") "CR1206-F/-2R70ELF")
        (field (name "MOUSER PART NUMBER") "652-CR1206-F/2R70ELF")
      )
      (libsource (lib "") (part "CR1206-F_-2R70ELF_2"))
    )
    (comp (ref "R6")
      (value "CR1206-4.7k")
      (footprint "PcbLib1:RESC3216X75N")
      (description "Resistor")
      (fields
        (field (name "MANUFACTURER_PART_NUMBER") "CR1206-F/-2R70ELF")
        (field (name "MOUSER PART NUMBER") "652-CR1206-F/2R70ELF")
      )
      (libsource (lib "") (part "CR1206-F_-2R70ELF_2"))
    )
    (comp (ref "R7")
      (value "CR1206-4.7k")
      (footprint "PcbLib1:RESC3216X75N")
      (description "Resistor")
      (fields
        (field (name "MANUFACTURER_PART_NUMBER") "CR1206-F/-2R70ELF")
        (field (name "MOUSER PART NUMBER") "652-CR1206-F/2R70ELF")
      )
      (libsource (lib "") (part "CR1206-F_-2R70ELF_1"))
    )
    (comp (ref "R8")
      (value "CR1206-4.7k")
      (footprint "PcbLib1:RESC3216X75N")
      (description "Resistor")
      (fields
        (field (name "MANUFACTURER_PART_NUMBER") "CR1206-F/-2R70ELF")
        (field (name "MOUSER PART NUMBER") "652-CR1206-F/2R70ELF")
      )
      (libsource (lib "") (part "CR1206-F_-2R70ELF_1"))
    )
    (comp (ref "R9")
      (value "CR1206-10k")
      (footprint "PcbLib1:RESC3216X75N")
      (description "Resistor")
      (fields
        (field (name "MANUFACTURER_PART_NUMBER") "CR1206-F/-2R70ELF")
        (field (name "MOUSER PART NUMBER") "652-CR1206-F/2R70ELF")
      )
      (libsource (lib "Schlib1") (part "CR1206-F_-2R70ELF"))
    )
    (comp (ref "R10")
      (value "CR1206-4.7k")
      (footprint "PcbLib1:RESC3216X75N")
      (description "Resistor")
      (fields
        (field (name "MANUFACTURER_PART_NUMBER") "CR1206-F/-2R70ELF")
        (field (name "MOUSER PART NUMBER") "652-CR1206-F/2R70ELF")
      )
      (libsource (lib "") (part "CR1206-F_-2R70ELF_1"))
    )
    (comp (ref "R11")
      (value "CR1206-4.7k")
      (footprint "PcbLib1:RESC3216X75N")
      (description "Resistor")
      (fields
        (field (name "MANUFACTURER_PART_NUMBER") "CR1206-F/-2R70ELF")
        (field (name "MOUSER PART NUMBER") "652-CR1206-F/2R70ELF")
      )
      (libsource (lib "") (part "CR1206-F_-2R70ELF_1"))
    )
    (comp (ref "R12")
      (value "CR1206-10k")
      (footprint "PcbLib1:RESC3216X75N")
      (description "Resistor")
      (fields
        (field (name "MANUFACTURER_PART_NUMBER") "CR1206-F/-2R70ELF")
        (field (name "MOUSER PART NUMBER") "652-CR1206-F/2R70ELF")
      )
      (libsource (lib "Schlib1") (part "CR1206-F_-2R70ELF"))
    )
    (comp (ref "R13")
      (value "CR1206-4.7k")
      (footprint "PcbLib1:RESC3216X75N")
      (description "Resistor")
      (fields
        (field (name "MANUFACTURER_PART_NUMBER") "CR1206-F/-2R70ELF")
        (field (name "MOUSER PART NUMBER") "652-CR1206-F/2R70ELF")
      )
      (libsource (lib "") (part "CR1206-F_-2R70ELF_1"))
    )
    (comp (ref "R14")
      (value "CR1206-4.7k")
      (footprint "PcbLib1:RESC3216X75N")
      (description "Resistor")
      (fields
        (field (name "MANUFACTURER_PART_NUMBER") "CR1206-F/-2R70ELF")
        (field (name "MOUSER PART NUMBER") "652-CR1206-F/2R70ELF")
      )
      (libsource (lib "") (part "CR1206-F_-2R70ELF_1"))
    )
    (comp (ref "R15")
      (value "CR1206-10k")
      (footprint "PcbLib1:RESC3216X75N")
      (description "Resistor")
      (fields
        (field (name "MANUFACTURER_PART_NUMBER") "CR1206-F/-2R70ELF")
        (field (name "MOUSER PART NUMBER") "652-CR1206-F/2R70ELF")
      )
      (libsource (lib "Schlib1") (part "CR1206-F_-2R70ELF"))
    )
    (comp (ref "R16")
      (value "CR1206-4.7k")
      (footprint "PcbLib1:RESC3216X75N")
      (description "Resistor")
      (fields
        (field (name "MANUFACTURER_PART_NUMBER") "CR1206-F/-2R70ELF")
        (field (name "MOUSER PART NUMBER") "652-CR1206-F/2R70ELF")
      )
      (libsource (lib "") (part "CR1206-F_-2R70ELF_1"))
    )
    (comp (ref "R17")
      (value "CR1206-4.7k")
      (footprint "PcbLib1:RESC3216X75N")
      (description "Resistor")
      (fields
        (field (name "MANUFACTURER_PART_NUMBER") "CR1206-F/-2R70ELF")
        (field (name "MOUSER PART NUMBER") "652-CR1206-F/2R70ELF")
      )
      (libsource (lib "") (part "CR1206-F_-2R70ELF_1"))
    )
    (comp (ref "R18")
      (value "CR1206-10k")
      (footprint "PcbLib1:RESC3216X75N")
      (description "Resistor")
      (fields
        (field (name "MANUFACTURER_PART_NUMBER") "CR1206-F/-2R70ELF")
        (field (name "MOUSER PART NUMBER") "652-CR1206-F/2R70ELF")
      )
      (libsource (lib "Schlib1") (part "CR1206-F_-2R70ELF"))
    )
    (comp (ref "R19")
      (value "CR1206-4.7k")
      (footprint "PcbLib1:RESC3216X75N")
      (description "Resistor")
      (fields
        (field (name "MANUFACTURER_PART_NUMBER") "CR1206-F/-2R70ELF")
        (field (name "MOUSER PART NUMBER") "652-CR1206-F/2R70ELF")
      )
      (libsource (lib "") (part "CR1206-F_-2R70ELF_1"))
    )
    (comp (ref "R20")
      (value "CR1206-4.7k")
      (footprint "PcbLib1:RESC3216X75N")
      (description "Resistor")
      (fields
        (field (name "MANUFACTURER_PART_NUMBER") "CR1206-F/-2R70ELF")
        (field (name "MOUSER PART NUMBER") "652-CR1206-F/2R70ELF")
      )
      (libsource (lib "") (part "CR1206-F_-2R70ELF_1"))
    )
    (comp (ref "R21")
      (value "CR1206-10k")
      (footprint "PcbLib1:RESC3216X75N")
      (description "Resistor")
      (fields
        (field (name "MANUFACTURER_PART_NUMBER") "CR1206-F/-2R70ELF")
        (field (name "MOUSER PART NUMBER") "652-CR1206-F/2R70ELF")
      )
      (libsource (lib "Schlib1") (part "CR1206-F_-2R70ELF"))
    )
    (comp (ref "R22")
      (value "CR1206-4.7k")
      (footprint "PcbLib1:RESC3216X75N")
      (description "Resistor")
      (fields
        (field (name "MANUFACTURER_PART_NUMBER") "CR1206-F/-2R70ELF")
        (field (name "MOUSER PART NUMBER") "652-CR1206-F/2R70ELF")
      )
      (libsource (lib "") (part "CR1206-F_-2R70ELF_1"))
    )
    (comp (ref "R23")
      (value "CR1206-4.7k")
      (footprint "PcbLib1:RESC3216X75N")
      (description "Resistor")
      (fields
        (field (name "MANUFACTURER_PART_NUMBER") "CR1206-F/-2R70ELF")
        (field (name "MOUSER PART NUMBER") "652-CR1206-F/2R70ELF")
      )
      (libsource (lib "") (part "CR1206-F_-2R70ELF_1"))
    )
    (comp (ref "R24")
      (value "CR1206-10k")
      (footprint "PcbLib1:RESC3216X75N")
      (description "Resistor")
      (fields
        (field (name "MANUFACTURER_PART_NUMBER") "CR1206-F/-2R70ELF")
        (field (name "MOUSER PART NUMBER") "652-CR1206-F/2R70ELF")
      )
      (libsource (lib "Schlib1") (part "CR1206-F_-2R70ELF"))
    )
    (comp (ref "R25")
      (value "453k 0805")
      (footprint "PcbLib2:RESC2012X65N")
      (description "Resistor")
      (fields
        (field (name "MANUFACTURER_PART_NUMBER") "CPF0805B100RE1")
        (field (name "MOUSER PART NUMBER") "279-CPF0805B100RE1")
      )
      (libsource (lib "") (part "CPF0805B100RE1_1"))
    )
    (comp (ref "R26")
      (value "CR1206-3.3k")
      (footprint "PcbLib1:RESC3216X75N")
      (description "Resistor")
      (fields
        (field (name "MANUFACTURER_PART_NUMBER") "CR1206-F/-2R70ELF")
        (field (name "MOUSER PART NUMBER") "652-CR1206-F/2R70ELF")
      )
      (libsource (lib "") (part "CR1206-F_-2R70ELF_2"))
    )
    (comp (ref "R27")
      (value "CR1206-4.7k")
      (footprint "PcbLib1:RESC3216X75N")
      (description "Resistor")
      (fields
        (field (name "MANUFACTURER_PART_NUMBER") "CR1206-F/-2R70ELF")
        (field (name "MOUSER PART NUMBER") "652-CR1206-F/2R70ELF")
      )
      (libsource (lib "") (part "CR1206-F_-2R70ELF_2"))
    )
    (comp (ref "R28")
      (value "CR1206-4.7k")
      (footprint "PcbLib1:RESC3216X75N")
      (description "Resistor")
      (fields
        (field (name "MANUFACTURER_PART_NUMBER") "CR1206-F/-2R70ELF")
        (field (name "MOUSER PART NUMBER") "652-CR1206-F/2R70ELF")
      )
      (libsource (lib "") (part "CR1206-F_-2R70ELF_2"))
    )
    (comp (ref "R29")
      (value "CR1206-4.7k")
      (footprint "PcbLib1:RESC3216X75N")
      (description "Resistor")
      (fields
        (field (name "MANUFACTURER_PART_NUMBER") "CR1206-F/-2R70ELF")
        (field (name "MOUSER PART NUMBER") "652-CR1206-F/2R70ELF")
      )
      (libsource (lib "") (part "CR1206-F_-2R70ELF_2"))
    )
    (comp (ref "R30")
      (value "CR1206-4.7k")
      (footprint "PcbLib1:RESC3216X75N")
      (description "Resistor")
      (fields
        (field (name "MANUFACTURER_PART_NUMBER") "CR1206-F/-2R70ELF")
        (field (name "MOUSER PART NUMBER") "652-CR1206-F/2R70ELF")
      )
      (libsource (lib "") (part "CR1206-F_-2R70ELF_1"))
    )
    (comp (ref "R31")
      (value "CR1206-4.7k")
      (footprint "PcbLib1:RESC3216X75N")
      (description "Resistor")
      (fields
        (field (name "MANUFACTURER_PART_NUMBER") "CR1206-F/-2R70ELF")
        (field (name "MOUSER PART NUMBER") "652-CR1206-F/2R70ELF")
      )
      (libsource (lib "") (part "CR1206-F_-2R70ELF_1"))
    )
    (comp (ref "R32")
      (value "CR1206-4.7k")
      (footprint "PcbLib1:RESC3216X75N")
      (description "Resistor")
      (fields
        (field (name "MANUFACTURER_PART_NUMBER") "CR1206-F/-2R70ELF")
        (field (name "MOUSER PART NUMBER") "652-CR1206-F/2R70ELF")
      )
      (libsource (lib "") (part "CR1206-F_-2R70ELF_1"))
    )
    (comp (ref "R33")
      (value "CR1206-4.7k")
      (footprint "PcbLib1:RESC3216X75N")
      (description "Resistor")
      (fields
        (field (name "MANUFACTURER_PART_NUMBER") "CR1206-F/-2R70ELF")
        (field (name "MOUSER PART NUMBER") "652-CR1206-F/2R70ELF")
      )
      (libsource (lib "") (part "CR1206-F_-2R70ELF_2"))
    )
    (comp (ref "R34")
      (value "453k 0805")
      (footprint "PcbLib2:RESC2012X65N")
      (description "Resistor")
      (fields
        (field (name "MANUFACTURER_PART_NUMBER") "CPF0805B100RE1")
        (field (name "MOUSER PART NUMBER") "279-CPF0805B100RE1")
      )
      (libsource (lib "Schlib1") (part "CPF0805B100RE1"))
    )
    (comp (ref "R35")
      (value "100k 0805")
      (footprint "PcbLib2:RESC2012X65N")
      (description "Resistor")
      (fields
        (field (name "MANUFACTURER_PART_NUMBER") "CPF0805B100RE1")
        (field (name "MOUSER PART NUMBER") "279-CPF0805B100RE1")
      )
      (libsource (lib "Schlib1") (part "CPF0805B100RE1"))
    )
    (comp (ref "R36")
      (value "49.9k ohm 0805")
      (footprint "PcbLib2:RESC2012X65N")
      (description "Resistor")
      (fields
        (field (name "MANUFACTURER_PART_NUMBER") "CPF0805B100RE1")
        (field (name "MOUSER PART NUMBER") "279-CPF0805B100RE1")
      )
      (libsource (lib "Schlib1") (part "CPF0805B100RE1"))
    )
    (comp (ref "R37")
      (value "CPF0805B100RE1_1")
      (footprint "PcbLib1:RESC2012X65N")
      (description "Resistor")
      (fields
        (field (name "MANUFACTURER_PART_NUMBER") "CPF0805B100RE1")
        (field (name "MOUSER PART NUMBER") "279-CPF0805B100RE1")
      )
      (libsource (lib "Schlib1") (part "CPF0805B100RE1_1"))
    )
    (comp (ref "R38")
      (value "CPF0805B100RE1_1")
      (footprint "PcbLib1:RESC2012X65N")
      (description "Resistor")
      (fields
        (field (name "MANUFACTURER_PART_NUMBER") "CPF0805B100RE1")
        (field (name "MOUSER PART NUMBER") "279-CPF0805B100RE1")
      )
      (libsource (lib "Schlib1") (part "CPF0805B100RE1_1"))
    )
    (comp (ref "R39")
      (value "CPF0805B100RE1_1")
      (footprint "PcbLib1:RESC2012X65N")
      (description "Resistor")
      (fields
        (field (name "MANUFACTURER_PART_NUMBER") "CPF0805B100RE1")
        (field (name "MOUSER PART NUMBER") "279-CPF0805B100RE1")
      )
      (libsource (lib "") (part "CPF0805B100RE1_1_1"))
    )
    (comp (ref "R40")
      (value "CPF0805B100RE1_1")
      (footprint "PcbLib1:RESC2012X65N")
      (description "Resistor")
      (fields
        (field (name "MANUFACTURER_PART_NUMBER") "CPF0805B100RE1")
        (field (name "MOUSER PART NUMBER") "279-CPF0805B100RE1")
      )
      (libsource (lib "") (part "CPF0805B100RE1_1_1"))
    )
    (comp (ref "R41")
      (value "CPF0805B100RE1")
      (footprint "PcbLib2:RESC2012X65N")
      (description "Resistor")
      (fields (field (name "MOUSER PART NUMBER") "279-CPF0805B100RE1"))
      (libsource (lib "") (part "CPF0805B100RE1_2"))
    )
    (comp (ref "R42")
      (value "0805 res")
      (footprint "PcbLib2:RESC2012X65N")
      (description "Resistor")
      (fields
        (field (name "MANUFACTURER_PART_NUMBER") "CPF0805B100RE1")
        (field (name "MOUSER PART NUMBER") "279-CPF0805B100RE1")
      )
      (libsource (lib "") (part "CPF0805B100RE1_3"))
    )
    (comp (ref "R43")
      (value "CR1206-220k")
      (footprint "PcbLib1:RESC3216X75N")
      (description "Resistor")
      (fields
        (field (name "MANUFACTURER_PART_NUMBER") "CR1206-F/-2R70ELF")
        (field (name "MOUSER PART NUMBER") "652-CR1206-F/2R70ELF")
      )
      (libsource (lib "Schlib1") (part "CR1206-F_-2R70ELF_1"))
    )
    (comp (ref "R44")
      (value "CR1206-4.7k")
      (footprint "PcbLib1:RESC3216X75N")
      (description "Resistor")
      (fields
        (field (name "MANUFACTURER_PART_NUMBER") "CR1206-F/-2R70ELF")
        (field (name "MOUSER PART NUMBER") "652-CR1206-F/2R70ELF")
      )
      (libsource (lib "Schlib1") (part "CR1206-F_-2R70ELF_1"))
    )
    (comp (ref "R45")
      (value "CPF0805 20k ohm")
      (footprint "PcbLib2:RESC2012X65N")
      (description "Resistor")
      (fields
        (field (name "MANUFACTURER_PART_NUMBER") "CPF0805B100RE1")
        (field (name "MOUSER PART NUMBER") "279-CPF0805B100RE1")
      )
      (libsource (lib "") (part "CPF0805B100RE1_2"))
    )
    (comp (ref "R46")
      (value "CPF0805 150 ohm")
      (footprint "PcbLib2:RESC2012X65N")
      (description "Resistor")
      (fields
        (field (name "MANUFACTURER_PART_NUMBER") "CPF0805B100RE1")
        (field (name "MOUSER PART NUMBER") "279-CPF0805B100RE1")
      )
      (libsource (lib "") (part "CPF0805B100RE1_3"))
    )
    (comp (ref "R47")
      (value "CPF0805 49.9k ohm")
      (footprint "PcbLib2:RESC2012X65N")
      (description "Resistor")
      (fields
        (field (name "MANUFACTURER_PART_NUMBER") "CPF0805B100RE1")
        (field (name "MOUSER PART NUMBER") "279-CPF0805B100RE1")
      )
      (libsource (lib "") (part "CPF0805B100RE1_2"))
    )
    (comp (ref "R48")
      (value "0805 res")
      (footprint "PcbLib2:RESC2012X65N")
      (description "Resistor")
      (fields
        (field (name "MANUFACTURER_PART_NUMBER") "CPF0805B100RE1")
        (field (name "MOUSER PART NUMBER") "279-CPF0805B100RE1")
      )
      (libsource (lib "") (part "CPF0805B100RE1_2"))
    )
    (comp (ref "R49")
      (value "CR1206-4.7k")
      (footprint "PcbLib1:RESC3216X75N")
      (description "Resistor")
      (fields
        (field (name "MANUFACTURER_PART_NUMBER") "CR1206-F/-2R70ELF")
        (field (name "MOUSER PART NUMBER") "652-CR1206-F/2R70ELF")
      )
      (libsource (lib "") (part "CR1206-F_-2R70ELF_1"))
    )
    (comp (ref "R50")
      (value "CR1206-4.7k")
      (footprint "PcbLib1:RESC3216X75N")
      (description "Resistor")
      (fields
        (field (name "MANUFACTURER_PART_NUMBER") "CR1206-F/-2R70ELF")
        (field (name "MOUSER PART NUMBER") "652-CR1206-F/2R70ELF")
      )
      (libsource (lib "") (part "CR1206-F_-2R70ELF_1"))
    )
    (comp (ref "R51")
      (value "CR1206-10k")
      (footprint "PcbLib1:RESC3216X75N")
      (description "Resistor")
      (fields
        (field (name "MANUFACTURER_PART_NUMBER") "CR1206-F/-2R70ELF")
        (field (name "MOUSER PART NUMBER") "652-CR1206-F/2R70ELF")
      )
      (libsource (lib "Schlib1") (part "CR1206-F_-2R70ELF"))
    )
    (comp (ref "R52")
      (value "CR1206-4.7k")
      (footprint "PcbLib1:RESC3216X75N")
      (description "Resistor")
      (fields
        (field (name "MANUFACTURER_PART_NUMBER") "CR1206-F/-2R70ELF")
        (field (name "MOUSER PART NUMBER") "652-CR1206-F/2R70ELF")
      )
      (libsource (lib "") (part "CR1206-F_-2R70ELF_1"))
    )
    (comp (ref "R53")
      (value "CR1206-4.7k")
      (footprint "PcbLib1:RESC3216X75N")
      (description "Resistor")
      (fields
        (field (name "MANUFACTURER_PART_NUMBER") "CR1206-F/-2R70ELF")
        (field (name "MOUSER PART NUMBER") "652-CR1206-F/2R70ELF")
      )
      (libsource (lib "") (part "CR1206-F_-2R70ELF_1"))
    )
    (comp (ref "R54")
      (value "CR1206-10k")
      (footprint "PcbLib1:RESC3216X75N")
      (description "Resistor")
      (fields
        (field (name "MANUFACTURER_PART_NUMBER") "CR1206-F/-2R70ELF")
        (field (name "MOUSER PART NUMBER") "652-CR1206-F/2R70ELF")
      )
      (libsource (lib "Schlib1") (part "CR1206-F_-2R70ELF"))
    )
    (comp (ref "R55")
      (value "CR1206-4.7k")
      (footprint "PcbLib1:RESC3216X75N")
      (description "Resistor")
      (fields
        (field (name "MANUFACTURER_PART_NUMBER") "CR1206-F/-2R70ELF")
        (field (name "MOUSER PART NUMBER") "652-CR1206-F/2R70ELF")
      )
      (libsource (lib "") (part "CR1206-F_-2R70ELF_1"))
    )
    (comp (ref "R56")
      (value "CR1206-4.7k")
      (footprint "PcbLib1:RESC3216X75N")
      (description "Resistor")
      (fields
        (field (name "MANUFACTURER_PART_NUMBER") "CR1206-F/-2R70ELF")
        (field (name "MOUSER PART NUMBER") "652-CR1206-F/2R70ELF")
      )
      (libsource (lib "") (part "CR1206-F_-2R70ELF_1"))
    )
    (comp (ref "R57")
      (value "CR1206-10k")
      (footprint "PcbLib1:RESC3216X75N")
      (description "Resistor")
      (fields
        (field (name "MANUFACTURER_PART_NUMBER") "CR1206-F/-2R70ELF")
        (field (name "MOUSER PART NUMBER") "652-CR1206-F/2R70ELF")
      )
      (libsource (lib "Schlib1") (part "CR1206-F_-2R70ELF"))
    )
    (comp (ref "R58")
      (value "CR1206-4.7k")
      (footprint "PcbLib1:RESC3216X75N")
      (description "Resistor")
      (fields
        (field (name "MANUFACTURER_PART_NUMBER") "CR1206-F/-2R70ELF")
        (field (name "MOUSER PART NUMBER") "652-CR1206-F/2R70ELF")
      )
      (libsource (lib "") (part "CR1206-F_-2R70ELF_1"))
    )
    (comp (ref "R59")
      (value "CR1206-4.7k")
      (footprint "PcbLib1:RESC3216X75N")
      (description "Resistor")
      (fields
        (field (name "MANUFACTURER_PART_NUMBER") "CR1206-F/-2R70ELF")
        (field (name "MOUSER PART NUMBER") "652-CR1206-F/2R70ELF")
      )
      (libsource (lib "") (part "CR1206-F_-2R70ELF_1"))
    )
    (comp (ref "R60")
      (value "CR1206-10k")
      (footprint "PcbLib1:RESC3216X75N")
      (description "Resistor")
      (fields
        (field (name "MANUFACTURER_PART_NUMBER") "CR1206-F/-2R70ELF")
        (field (name "MOUSER PART NUMBER") "652-CR1206-F/2R70ELF")
      )
      (libsource (lib "Schlib1") (part "CR1206-F_-2R70ELF"))
    )
    (comp (ref "R61")
      (value "CR1206-4.7k")
      (footprint "PcbLib1:RESC3216X75N")
      (description "Resistor")
      (fields
        (field (name "MANUFACTURER_PART_NUMBER") "CR1206-F/-2R70ELF")
        (field (name "MOUSER PART NUMBER") "652-CR1206-F/2R70ELF")
      )
      (libsource (lib "") (part "CR1206-F_-2R70ELF_1"))
    )
    (comp (ref "R62")
      (value "CR1206-4.7k")
      (footprint "PcbLib1:RESC3216X75N")
      (description "Resistor")
      (fields
        (field (name "MANUFACTURER_PART_NUMBER") "CR1206-F/-2R70ELF")
        (field (name "MOUSER PART NUMBER") "652-CR1206-F/2R70ELF")
      )
      (libsource (lib "") (part "CR1206-F_-2R70ELF_1"))
    )
    (comp (ref "R63")
      (value "CR1206-10k")
      (footprint "PcbLib1:RESC3216X75N")
      (description "Resistor")
      (fields
        (field (name "MANUFACTURER_PART_NUMBER") "CR1206-F/-2R70ELF")
        (field (name "MOUSER PART NUMBER") "652-CR1206-F/2R70ELF")
      )
      (libsource (lib "Schlib1") (part "CR1206-F_-2R70ELF"))
    )
    (comp (ref "R64")
      (value "CR1206-4.7k")
      (footprint "PcbLib1:RESC3216X75N")
      (description "Resistor")
      (fields
        (field (name "MANUFACTURER_PART_NUMBER") "CR1206-F/-2R70ELF")
        (field (name "MOUSER PART NUMBER") "652-CR1206-F/2R70ELF")
      )
      (libsource (lib "") (part "CR1206-F_-2R70ELF_1"))
    )
    (comp (ref "R65")
      (value "CR1206-4.7k")
      (footprint "PcbLib1:RESC3216X75N")
      (description "Resistor")
      (fields
        (field (name "MANUFACTURER_PART_NUMBER") "CR1206-F/-2R70ELF")
        (field (name "MOUSER PART NUMBER") "652-CR1206-F/2R70ELF")
      )
      (libsource (lib "") (part "CR1206-F_-2R70ELF_1"))
    )
    (comp (ref "R66")
      (value "CR1206-10k")
      (footprint "PcbLib1:RESC3216X75N")
      (description "Resistor")
      (fields
        (field (name "MANUFACTURER_PART_NUMBER") "CR1206-F/-2R70ELF")
        (field (name "MOUSER PART NUMBER") "652-CR1206-F/2R70ELF")
      )
      (libsource (lib "Schlib1") (part "CR1206-F_-2R70ELF"))
    )
    (comp (ref "R67")
      (value "CR1206-4.7k")
      (footprint "PcbLib1:RESC3216X75N")
      (description "Resistor")
      (fields
        (field (name "MANUFACTURER_PART_NUMBER") "CR1206-F/-2R70ELF")
        (field (name "MOUSER PART NUMBER") "652-CR1206-F/2R70ELF")
      )
      (libsource (lib "") (part "CR1206-F_-2R70ELF_1"))
    )
    (comp (ref "R68")
      (value "CR1206-4.7k")
      (footprint "PcbLib1:RESC3216X75N")
      (description "Resistor")
      (fields
        (field (name "MANUFACTURER_PART_NUMBER") "CR1206-F/-2R70ELF")
        (field (name "MOUSER PART NUMBER") "652-CR1206-F/2R70ELF")
      )
      (libsource (lib "") (part "CR1206-F_-2R70ELF_1"))
    )
    (comp (ref "R69")
      (value "CR1206-10k")
      (footprint "PcbLib1:RESC3216X75N")
      (description "Resistor")
      (fields
        (field (name "MANUFACTURER_PART_NUMBER") "CR1206-F/-2R70ELF")
        (field (name "MOUSER PART NUMBER") "652-CR1206-F/2R70ELF")
      )
      (libsource (lib "Schlib1") (part "CR1206-F_-2R70ELF"))
    )
    (comp (ref "R70")
      (value "CR1206-4.7k")
      (footprint "PcbLib1:RESC3216X75N")
      (description "Resistor")
      (fields
        (field (name "MANUFACTURER_PART_NUMBER") "CR1206-F/-2R70ELF")
        (field (name "MOUSER PART NUMBER") "652-CR1206-F/2R70ELF")
      )
      (libsource (lib "") (part "CR1206-F_-2R70ELF_1"))
    )
    (comp (ref "R71")
      (value "CR1206-4.7k")
      (footprint "PcbLib1:RESC3216X75N")
      (description "Resistor")
      (fields
        (field (name "MANUFACTURER_PART_NUMBER") "CR1206-F/-2R70ELF")
        (field (name "MOUSER PART NUMBER") "652-CR1206-F/2R70ELF")
      )
      (libsource (lib "") (part "CR1206-F_-2R70ELF_1"))
    )
    (comp (ref "R72")
      (value "CR1206-10k")
      (footprint "PcbLib1:RESC3216X75N")
      (description "Resistor")
      (fields
        (field (name "MANUFACTURER_PART_NUMBER") "CR1206-F/-2R70ELF")
        (field (name "MOUSER PART NUMBER") "652-CR1206-F/2R70ELF")
      )
      (libsource (lib "Schlib1") (part "CR1206-F_-2R70ELF"))
    )
    (comp (ref "R73")
      (value "CR1206-4.7k")
      (footprint "PcbLib1:RESC3216X75N")
      (description "Resistor")
      (fields
        (field (name "MANUFACTURER_PART_NUMBER") "CR1206-F/-2R70ELF")
        (field (name "MOUSER PART NUMBER") "652-CR1206-F/2R70ELF")
      )
      (libsource (lib "") (part "CR1206-F_-2R70ELF_1"))
    )
    (comp (ref "R74")
      (value "CR1206-4.7k")
      (footprint "PcbLib1:RESC3216X75N")
      (description "Resistor")
      (fields
        (field (name "MANUFACTURER_PART_NUMBER") "CR1206-F/-2R70ELF")
        (field (name "MOUSER PART NUMBER") "652-CR1206-F/2R70ELF")
      )
      (libsource (lib "") (part "CR1206-F_-2R70ELF_1"))
    )
    (comp (ref "R75")
      (value "CR1206-10k")
      (footprint "PcbLib1:RESC3216X75N")
      (description "Resistor")
      (fields
        (field (name "MANUFACTURER_PART_NUMBER") "CR1206-F/-2R70ELF")
        (field (name "MOUSER PART NUMBER") "652-CR1206-F/2R70ELF")
      )
      (libsource (lib "Schlib1") (part "CR1206-F_-2R70ELF"))
    )
    (comp (ref "R76")
      (value "CR1206-4.7k")
      (footprint "PcbLib1:RESC3216X75N")
      (description "Resistor")
      (fields
        (field (name "MANUFACTURER_PART_NUMBER") "CR1206-F/-2R70ELF")
        (field (name "MOUSER PART NUMBER") "652-CR1206-F/2R70ELF")
      )
      (libsource (lib "") (part "CR1206-F_-2R70ELF_1"))
    )
    (comp (ref "R77")
      (value "CR1206-4.7k")
      (footprint "PcbLib1:RESC3216X75N")
      (description "Resistor")
      (fields
        (field (name "MANUFACTURER_PART_NUMBER") "CR1206-F/-2R70ELF")
        (field (name "MOUSER PART NUMBER") "652-CR1206-F/2R70ELF")
      )
      (libsource (lib "") (part "CR1206-F_-2R70ELF_1"))
    )
    (comp (ref "R78")
      (value "CR1206-10k")
      (footprint "PcbLib1:RESC3216X75N")
      (description "Resistor")
      (fields
        (field (name "MANUFACTURER_PART_NUMBER") "CR1206-F/-2R70ELF")
        (field (name "MOUSER PART NUMBER") "652-CR1206-F/2R70ELF")
      )
      (libsource (lib "Schlib1") (part "CR1206-F_-2R70ELF"))
    )
    (comp (ref "R79")
      (value "CR1206-4.7k")
      (footprint "PcbLib1:RESC3216X75N")
      (description "Resistor")
      (fields
        (field (name "MANUFACTURER_PART_NUMBER") "CR1206-F/-2R70ELF")
        (field (name "MOUSER PART NUMBER") "652-CR1206-F/2R70ELF")
      )
      (libsource (lib "") (part "CR1206-F_-2R70ELF_1"))
    )
    (comp (ref "R80")
      (value "CR1206-4.7k")
      (footprint "PcbLib1:RESC3216X75N")
      (description "Resistor")
      (fields
        (field (name "MANUFACTURER_PART_NUMBER") "CR1206-F/-2R70ELF")
        (field (name "MOUSER PART NUMBER") "652-CR1206-F/2R70ELF")
      )
      (libsource (lib "") (part "CR1206-F_-2R70ELF_1"))
    )
    (comp (ref "R81")
      (value "CR1206-10k")
      (footprint "PcbLib1:RESC3216X75N")
      (description "Resistor")
      (fields
        (field (name "MANUFACTURER_PART_NUMBER") "CR1206-F/-2R70ELF")
        (field (name "MOUSER PART NUMBER") "652-CR1206-F/2R70ELF")
      )
      (libsource (lib "Schlib1") (part "CR1206-F_-2R70ELF"))
    )
    (comp (ref "R82")
      (value "CR1206-4.7k")
      (footprint "PcbLib1:RESC3216X75N")
      (description "Resistor")
      (fields
        (field (name "MANUFACTURER_PART_NUMBER") "CR1206-F/-2R70ELF")
        (field (name "MOUSER PART NUMBER") "652-CR1206-F/2R70ELF")
      )
      (libsource (lib "") (part "CR1206-F_-2R70ELF_1"))
    )
    (comp (ref "R83")
      (value "CR1206-4.7k")
      (footprint "PcbLib1:RESC3216X75N")
      (description "Resistor")
      (fields
        (field (name "MANUFACTURER_PART_NUMBER") "CR1206-F/-2R70ELF")
        (field (name "MOUSER PART NUMBER") "652-CR1206-F/2R70ELF")
      )
      (libsource (lib "") (part "CR1206-F_-2R70ELF_1"))
    )
    (comp (ref "R84")
      (value "CR1206-10k")
      (footprint "PcbLib1:RESC3216X75N")
      (description "Resistor")
      (fields
        (field (name "MANUFACTURER_PART_NUMBER") "CR1206-F/-2R70ELF")
        (field (name "MOUSER PART NUMBER") "652-CR1206-F/2R70ELF")
      )
      (libsource (lib "Schlib1") (part "CR1206-F_-2R70ELF"))
    )
    (comp (ref "R85")
      (value "CR1206-4.7k")
      (footprint "PcbLib1:RESC3216X75N")
      (description "Resistor")
      (fields
        (field (name "MANUFACTURER_PART_NUMBER") "CR1206-F/-2R70ELF")
        (field (name "MOUSER PART NUMBER") "652-CR1206-F/2R70ELF")
      )
      (libsource (lib "") (part "CR1206-F_-2R70ELF_2"))
    )
    (comp (ref "R86")
      (value "CR1206-4.7k")
      (footprint "PcbLib1:RESC3216X75N")
      (description "Resistor")
      (fields
        (field (name "MANUFACTURER_PART_NUMBER") "CR1206-F/-2R70ELF")
        (field (name "MOUSER PART NUMBER") "652-CR1206-F/2R70ELF")
      )
      (libsource (lib "") (part "CR1206-F_-2R70ELF_1"))
    )
    (comp (ref "R87")
      (value "CR1206-3.3k")
      (footprint "PcbLib1:RESC3216X75N")
      (description "Resistor")
      (fields
        (field (name "MANUFACTURER_PART_NUMBER") "CR1206-F/-2R70ELF")
        (field (name "MOUSER PART NUMBER") "652-CR1206-F/2R70ELF")
      )
      (libsource (lib "") (part "CR1206-F_-2R70ELF_1"))
    )
    (comp (ref "R88")
      (value "CR1206-4.7k")
      (footprint "PcbLib1:RESC3216X75N")
      (description "Resistor")
      (fields
        (field (name "MANUFACTURER_PART_NUMBER") "CR1206-F/-2R70ELF")
        (field (name "MOUSER PART NUMBER") "652-CR1206-F/2R70ELF")
      )
      (libsource (lib "") (part "CR1206-F_-2R70ELF_2"))
    )
    (comp (ref "R89")
      (value "GENEL RES DİK")
      (footprint "DİK GENEL RES THT")
      (libsource (lib "Schlib1") (part "GENEL RES DİK"))
    )
    (comp (ref "R90")
      (value "GENEL RES DİK")
      (footprint "DİK GENEL RES THT")
      (libsource (lib "Schlib1") (part "GENEL RES DİK"))
    )
    (comp (ref "R91")
      (value "GENEL RES DİK")
      (footprint "DİK GENEL RES THT")
      (libsource (lib "Schlib1") (part "GENEL RES DİK"))
    )
    (comp (ref "S1")
      (value "1437566-4")
      (footprint "PcbLib2:14375664")
      (description "Switch")
      (libsource (lib "Schlib1") (part "1437566-4"))
    )
    (comp (ref "U1")
      (value "LD108633 3.3V DPAK")
      (footprint "DPAK228P972X240-3N")
      (description "LD108633 3.3V REGULATOR")
      (libsource (lib "Schlib1") (part "LD108633 3.3V DPAK"))
    )
    (comp (ref "U2")
      (value "L7805-DPAK_1")
      (footprint "DPAK228P972X240-3N")
      (description "L7805 5V REGULATOR. SMD PAKET")
      (libsource (lib "Schlib1") (part "L7805-DPAK_1"))
    )
    (comp (ref "VR1")
      (value "3296W-1-252LF")
      (footprint "SamacSys:3296W-1")
      (description "Variable Resistor")
      (fields (field (name "MOUSER PART NUMBER") "652-3296W-1-252LF"))
      (libsource (lib "Schlib1") (part "3296W-1-252LF"))
    )
    (comp (ref "W1")
      (value "kablo bara")
      (footprint "KABLO BARA")
      (description "KABLO BARA")
      (libsource (lib "Schlib1") (part "kablo bara"))
    )
    (comp (ref "X1")
      (value "8M Hz kristal")
      (footprint "8M Hz kristal")
      (libsource (lib "Schlib1") (part "8M Hz kristal"))
    )
    (comp (ref "Z1")
      (value "3SMAJ5927B-TP - ms110")
      (footprint "PcbLib1:DIOM5226X244N")
      (description "Zener Diode")
      (fields
        (field (name "MANUFACTURER_PART_NUMBER") "3SMAJ5927B-TP")
        (field (name "MOUSER PART NUMBER") "833-3SMAJ5927B-TP")
      )
      (libsource (lib "*") (part "3SMAJ5927B-TP"))
    )
    (comp (ref "Z2")
      (value "3SMAJ5927B-TP - ms110")
      (footprint "PcbLib1:DIOM5226X244N")
      (description "Zener Diode")
      (fields
        (field (name "MANUFACTURER_PART_NUMBER") "3SMAJ5927B-TP")
        (field (name "MOUSER PART NUMBER") "833-3SMAJ5927B-TP")
      )
      (libsource (lib "*") (part "3SMAJ5927B-TP"))
    )
    (comp (ref "Z3")
      (value "3SMAJ5927B-TP - ms110")
      (footprint "PcbLib1:DIOM5226X244N")
      (description "Zener Diode")
      (fields
        (field (name "MANUFACTURER_PART_NUMBER") "3SMAJ5927B-TP")
        (field (name "MOUSER PART NUMBER") "833-3SMAJ5927B-TP")
      )
      (libsource (lib "*") (part "3SMAJ5927B-TP"))
    )
    (comp (ref "Z4")
      (value "3SMAJ5927B-TP - ms110")
      (footprint "PcbLib1:DIOM5226X244N")
      (description "Zener Diode")
      (fields
        (field (name "MANUFACTURER_PART_NUMBER") "3SMAJ5927B-TP")
        (field (name "MOUSER PART NUMBER") "833-3SMAJ5927B-TP")
      )
      (libsource (lib "*") (part "3SMAJ5927B-TP"))
    )
    (comp (ref "Z5")
      (value "3SMAJ5927B-TP - ms110")
      (footprint "PcbLib1:DIOM5226X244N")
      (description "Zener Diode")
      (fields
        (field (name "MANUFACTURER_PART_NUMBER") "3SMAJ5927B-TP")
        (field (name "MOUSER PART NUMBER") "833-3SMAJ5927B-TP")
      )
      (libsource (lib "*") (part "3SMAJ5927B-TP"))
    )
    (comp (ref "Z6")
      (value "3SMAJ5927B-TP - ms110")
      (footprint "PcbLib1:DIOM5226X244N")
      (description "Zener Diode")
      (fields
        (field (name "MANUFACTURER_PART_NUMBER") "3SMAJ5927B-TP")
        (field (name "MOUSER PART NUMBER") "833-3SMAJ5927B-TP")
      )
      (libsource (lib "*") (part "3SMAJ5927B-TP"))
    )
    (comp (ref "Z7")
      (value "3SMAJ5927B-TP - ms110")
      (footprint "PcbLib1:DIOM5226X244N")
      (description "Zener Diode")
      (fields
        (field (name "MANUFACTURER_PART_NUMBER") "3SMAJ5927B-TP")
        (field (name "MOUSER PART NUMBER") "833-3SMAJ5927B-TP")
      )
      (libsource (lib "*") (part "3SMAJ5927B-TP"))
    )
    (comp (ref "Z8")
      (value "3SMAJ5927B-TP - ms110")
      (footprint "PcbLib1:DIOM5226X244N")
      (description "Zener Diode")
      (fields
        (field (name "MANUFACTURER_PART_NUMBER") "3SMAJ5927B-TP")
        (field (name "MOUSER PART NUMBER") "833-3SMAJ5927B-TP")
      )
      (libsource (lib "*") (part "3SMAJ5927B-TP"))
    )
    (comp (ref "Z9")
      (value "3SMAJ5927B-TP - ms110")
      (footprint "PcbLib1:DIOM5226X244N")
      (description "Zener Diode")
      (fields
        (field (name "MANUFACTURER_PART_NUMBER") "3SMAJ5927B-TP")
        (field (name "MOUSER PART NUMBER") "833-3SMAJ5927B-TP")
      )
      (libsource (lib "*") (part "3SMAJ5927B-TP"))
    )
    (comp (ref "Z10")
      (value "3SMAJ5927B-TP - ms110")
      (footprint "PcbLib1:DIOM5226X244N")
      (description "Zener Diode")
      (fields
        (field (name "MANUFACTURER_PART_NUMBER") "3SMAJ5927B-TP")
        (field (name "MOUSER PART NUMBER") "833-3SMAJ5927B-TP")
      )
      (libsource (lib "*") (part "3SMAJ5927B-TP"))
    )
    (comp (ref "Z11")
      (value "3SMAJ5927B-TP - ms110")
      (footprint "PcbLib1:DIOM5226X244N")
      (description "Zener Diode")
      (fields
        (field (name "MANUFACTURER_PART_NUMBER") "3SMAJ5927B-TP")
        (field (name "MOUSER PART NUMBER") "833-3SMAJ5927B-TP")
      )
      (libsource (lib "*") (part "3SMAJ5927B-TP"))
    )
    (comp (ref "Z12")
      (value "3SMAJ5927B-TP - ms110")
      (footprint "PcbLib1:DIOM5226X244N")
      (description "Zener Diode")
      (fields
        (field (name "MANUFACTURER_PART_NUMBER") "3SMAJ5927B-TP")
        (field (name "MOUSER PART NUMBER") "833-3SMAJ5927B-TP")
      )
      (libsource (lib "*") (part "3SMAJ5927B-TP"))
    )
    (comp (ref "Z13")
      (value "3SMAJ5927B-TP - ms110")
      (footprint "PcbLib1:DIOM5226X244N")
      (description "Zener Diode")
      (fields
        (field (name "MANUFACTURER_PART_NUMBER") "3SMAJ5927B-TP")
        (field (name "MOUSER PART NUMBER") "833-3SMAJ5927B-TP")
      )
      (libsource (lib "*") (part "3SMAJ5927B-TP"))
    )
    (comp (ref "Z14")
      (value "3SMAJ5927B-TP - ms110")
      (footprint "PcbLib1:DIOM5226X244N")
      (description "Zener Diode")
      (fields
        (field (name "MANUFACTURER_PART_NUMBER") "3SMAJ5927B-TP")
        (field (name "MOUSER PART NUMBER") "833-3SMAJ5927B-TP")
      )
      (libsource (lib "*") (part "3SMAJ5927B-TP"))
    )
    (comp (ref "Z15")
      (value "3SMAJ5927B-TP - ms110")
      (footprint "PcbLib1:DIOM5226X244N")
      (description "Zener Diode")
      (fields
        (field (name "MANUFACTURER_PART_NUMBER") "3SMAJ5927B-TP")
        (field (name "MOUSER PART NUMBER") "833-3SMAJ5927B-TP")
      )
      (libsource (lib "*") (part "3SMAJ5927B-TP"))
    )
    (comp (ref "Z16")
      (value "3SMAJ5927B-TP - ms110")
      (footprint "PcbLib1:DIOM5226X244N")
      (description "Zener Diode")
      (fields
        (field (name "MANUFACTURER_PART_NUMBER") "3SMAJ5927B-TP")
        (field (name "MOUSER PART NUMBER") "833-3SMAJ5927B-TP")
      )
      (libsource (lib "*") (part "3SMAJ5927B-TP"))
    )
    (comp (ref "Z17")
      (value "3SMAJ5927B-TP - ms110")
      (footprint "PcbLib1:DIOM5226X244N")
      (description "Zener Diode")
      (fields
        (field (name "MANUFACTURER_PART_NUMBER") "3SMAJ5927B-TP")
        (field (name "MOUSER PART NUMBER") "833-3SMAJ5927B-TP")
      )
      (libsource (lib "*") (part "3SMAJ5927B-TP"))
    )
    (comp (ref "Z18")
      (value "3SMAJ5927B-TP - ms110")
      (footprint "PcbLib1:DIOM5226X244N")
      (description "Zener Diode")
      (fields
        (field (name "MANUFACTURER_PART_NUMBER") "3SMAJ5927B-TP")
        (field (name "MOUSER PART NUMBER") "833-3SMAJ5927B-TP")
      )
      (libsource (lib "*") (part "3SMAJ5927B-TP"))
    )
  )
  (nets
    (net (code "1") (name "+12") (class "Default")
      (node (ref "C15") (pin "1") (pinfunction "1_1") (pintype "passive"))
      (node (ref "C17") (pin "1") (pinfunction "1_1") (pintype "passive"))
      (node (ref "C18") (pin "1") (pinfunction "1_1") (pintype "passive"))
      (node (ref "C21") (pin "1") (pinfunction "1_1") (pintype "passive"))
      (node (ref "C36") (pin "1") (pinfunction "1_1") (pintype "passive"))
      (node (ref "C39") (pin "1") (pinfunction "1_1") (pintype "passive"))
      (node (ref "C42") (pin "2") (pinfunction "2_2") (pintype "passive"))
      (node (ref "C43") (pin "1") (pinfunction "1_1") (pintype "passive"))
      (node (ref "C7") (pin "2") (pinfunction "2_2") (pintype "passive"))
      (node (ref "IC1") (pin "1") (pinfunction "VDD_1") (pintype "passive"))
      (node (ref "J10") (pin "1") (pinfunction "2_1") (pintype "passive"))
      (node (ref "L1") (pin "2") (pinfunction "2_2") (pintype "passive"))
      (node (ref "R34") (pin "1") (pinfunction "1_1") (pintype "passive"))
      (node (ref "U2") (pin "1") (pinfunction "VIN_1") (pintype "passive"))
      (node (ref "W1") (pin "1") (pinfunction "1_1") (pintype "passive"))
    )
    (net (code "2") (name "+12A") (class "Default")
      (node (ref "C40") (pin "1") (pinfunction "1_1") (pintype "passive"))
      (node (ref "C9") (pin "2") (pinfunction "2_2") (pintype "passive"))
      (node (ref "IC3") (pin "1") (pinfunction "VDD_1") (pintype "passive"))
      (node (ref "W1") (pin "2") (pinfunction "2_2") (pintype "passive"))
      (node (ref "W1") (pin "3") (pinfunction "3_3") (pintype "passive"))
    )
    (net (code "3") (name "+12B") (class "Default")
      (node (ref "C11") (pin "2") (pinfunction "2_2") (pintype "passive"))
      (node (ref "C41") (pin "1") (pinfunction "1_1") (pintype "passive"))
      (node (ref "C44") (pin "2") (pinfunction "2_2") (pintype "passive"))
      (node (ref "C45") (pin "1") (pinfunction "1_1") (pintype "passive"))
      (node (ref "IC4") (pin "1") (pinfunction "VDD_1") (pintype "passive"))
      (node (ref "J11") (pin "1") (pinfunction "2_1") (pintype "passive"))
      (node (ref "W1") (pin "4") (pinfunction "4_4") (pintype "passive"))
    )
    (net (code "4") (name "/3V3") (class "Default")
      (node (ref "C28") (pin "1") (pinfunction "1_1") (pintype "passive"))
      (node (ref "C34") (pin "2") (pinfunction "2_2") (pintype "passive"))
      (node (ref "C35") (pin "2") (pinfunction "2_2") (pintype "passive"))
      (node (ref "IC2") (pin "1") (pinfunction "VBAT_1") (pintype "passive"))
      (node (ref "IC2") (pin "24") (pinfunction "VDD_1_24") (pintype "passive"))
      (node (ref "IC2") (pin "36") (pinfunction "VDD_2_36") (pintype "passive"))
      (node (ref "IC2") (pin "48") (pinfunction "VDD_3_48") (pintype "passive"))
      (node (ref "IC2") (pin "9") (pinfunction "VDDA_9") (pintype "passive"))
      (node (ref "IC8") (pin "5") (pinfunction "VDD_5") (pintype "power_in"))
      (node (ref "IC9") (pin "14") (pinfunction "VCC_14") (pintype "passive"))
      (node (ref "R26") (pin "1") (pinfunction "1_1") (pintype "passive"))
      (node (ref "R27") (pin "1") (pinfunction "1_1") (pintype "passive"))
      (node (ref "R28") (pin "1") (pinfunction "1_1") (pintype "passive"))
      (node (ref "R29") (pin "1") (pinfunction "1_1") (pintype "passive"))
      (node (ref "R33") (pin "1") (pinfunction "1_1") (pintype "passive"))
      (node (ref "R41") (pin "2") (pinfunction "2_2") (pintype "passive"))
      (node (ref "R45") (pin "2") (pinfunction "2_2") (pintype "passive"))
      (node (ref "R88") (pin "1") (pinfunction "1_1") (pintype "passive"))
      (node (ref "U1") (pin "3") (pinfunction "VOUT_3") (pintype "passive"))
      (node (ref "VR1") (pin "3") (pinfunction "CW_3") (pintype "passive"))
      (node (ref "jst2") (pin "1") (pinfunction "1_1") (pintype "passive"))
    )
    (net (code "5") (name "/5V") (class "Default")
      (node (ref "C29") (pin "1") (pinfunction "1_1") (pintype "passive"))
      (node (ref "C33") (pin "2") (pinfunction "2_2") (pintype "passive"))
      (node (ref "C37") (pin "1") (pinfunction "1_1") (pintype "passive"))
      (node (ref "C38") (pin "2") (pinfunction "2_2") (pintype "passive"))
      (node (ref "IC5") (pin "3") (pinfunction "S_3") (pintype "passive"))
      (node (ref "IC7") (pin "3") (pinfunction "VDD_3") (pintype "passive"))
      (node (ref "J3") (pin "5") (pinfunction "5_5") (pintype "passive"))
      (node (ref "P1") (pin "1") (pinfunction "1_1") (pintype "passive"))
      (node (ref "R39") (pin "2") (pinfunction "2_2") (pintype "passive"))
      (node (ref "R40") (pin "2") (pinfunction "2_2") (pintype "passive"))
      (node (ref "U1") (pin "2") (pinfunction "VIN_2") (pintype "passive"))
      (node (ref "U2") (pin "2") (pinfunction "VOUT_2") (pintype "passive"))
      (node (ref "jst1") (pin "3") (pinfunction "3_3") (pintype "passive"))
      (node (ref "jst4") (pin "1") (pinfunction "1_1") (pintype "passive"))
      (node (ref "jst5") (pin "1") (pinfunction "1_1") (pintype "passive"))
    )
    (net (code "6") (name "/A") (class "Default")
      (node (ref "C27") (pin "2") (pinfunction "2_2") (pintype "passive"))
      (node (ref "IC9") (pin "5") (pinfunction "3A_5") (pintype "passive"))
      (node (ref "R29") (pin "2") (pinfunction "2_2") (pintype "passive"))
      (node (ref "R32") (pin "2") (pinfunction "2_2") (pintype "passive"))
      (node (ref "R47") (pin "2") (pinfunction "2_2") (pintype "passive"))
    )
    (net (code "7") (name "/A_MCU") (class "Default")
      (node (ref "IC2") (pin "12") (pinfunction "PA2_12") (pintype "passive"))
      (node (ref "IC9") (pin "6") (pinfunction "3Y_6") (pintype "passive"))
    )
    (net (code "8") (name "/B") (class "Default")
      (node (ref "C26") (pin "2") (pinfunction "2_2") (pintype "passive"))
      (node (ref "IC9") (pin "3") (pinfunction "2A_3") (pintype "passive"))
      (node (ref "R28") (pin "2") (pinfunction "2_2") (pintype "passive"))
      (node (ref "R31") (pin "2") (pinfunction "2_2") (pintype "passive"))
    )
    (net (code "9") (name "/B_MCU") (class "Default")
      (node (ref "IC2") (pin "11") (pinfunction "PA1_11") (pintype "passive"))
      (node (ref "IC9") (pin "4") (pinfunction "2Y_4") (pintype "passive"))
    )
    (net (code "10") (name "/C") (class "Default")
      (node (ref "C25") (pin "2") (pinfunction "2_2") (pintype "passive"))
      (node (ref "IC9") (pin "1") (pinfunction "1A_1") (pintype "passive"))
      (node (ref "R27") (pin "2") (pinfunction "2_2") (pintype "passive"))
      (node (ref "R30") (pin "2") (pinfunction "2_2") (pintype "passive"))
    )
    (net (code "11") (name "/CAN RX") (class "Default")
      (node (ref "IC2") (pin "32") (pinfunction "PA11_32") (pintype "passive"))
      (node (ref "IC7") (pin "4") (pinfunction "RXD_4") (pintype "passive"))
    )
    (net (code "12") (name "/CAN TX") (class "Default")
      (node (ref "IC2") (pin "33") (pinfunction "PA12_33") (pintype "passive"))
      (node (ref "IC7") (pin "1") (pinfunction "TXD_1") (pintype "passive"))
    )
    (net (code "13") (name "/CCW") (class "Default")
      (node (ref "IC2") (pin "13") (pinfunction "PA3_13") (pintype "passive"))
      (node (ref "J4") (pin "2") (pinfunction "9_2") (pintype "passive"))
      (node (ref "R33") (pin "2") (pinfunction "2_2") (pintype "passive"))
    )
    (net (code "14") (name "/C_MCU") (class "Default")
      (node (ref "IC2") (pin "10") (pinfunction "PA0-WKUP_10") (pintype "passive"))
      (node (ref "IC9") (pin "2") (pinfunction "1Y_2") (pintype "passive"))
    )
    (net (code "15") (name "/HG1") (class "Default")
      (node (ref "Q4") (pin "1") (pinfunction "G_1") (pintype "passive"))
      (node (ref "R8") (pin "2") (pinfunction "2_2") (pintype "passive"))
      (node (ref "R9") (pin "2") (pinfunction "2_2") (pintype "passive"))
      (node (ref "Z1") (pin "2") (pinfunction "A_2") (pintype "passive"))
    )
    (net (code "16") (name "/HG1B") (class "Default")
      (node (ref "Q8") (pin "1") (pinfunction "G_1") (pintype "passive"))
      (node (ref "R50") (pin "2") (pinfunction "2_2") (pintype "passive"))
      (node (ref "R51") (pin "2") (pinfunction "2_2") (pintype "passive"))
      (node (ref "Z7") (pin "2") (pinfunction "A_2") (pintype "passive"))
    )
    (net (code "17") (name "/HG1C") (class "Default")
      (node (ref "Q20") (pin "1") (pinfunction "G_1") (pintype "passive"))
      (node (ref "R68") (pin "2") (pinfunction "2_2") (pintype "passive"))
      (node (ref "R69") (pin "2") (pinfunction "2_2") (pintype "passive"))
      (node (ref "Z13") (pin "2") (pinfunction "A_2") (pintype "passive"))
    )
    (net (code "18") (name "/HG2") (class "Default")
      (node (ref "Q5") (pin "1") (pinfunction "G_1") (pintype "passive"))
      (node (ref "R14") (pin "2") (pinfunction "2_2") (pintype "passive"))
      (node (ref "R15") (pin "2") (pinfunction "2_2") (pintype "passive"))
      (node (ref "Z3") (pin "2") (pinfunction "A_2") (pintype "passive"))
    )
    (net (code "19") (name "/HG2B") (class "Default")
      (node (ref "Q2") (pin "1") (pinfunction "G_1") (pintype "passive"))
      (node (ref "R56") (pin "2") (pinfunction "2_2") (pintype "passive"))
      (node (ref "R57") (pin "2") (pinfunction "2_2") (pintype "passive"))
      (node (ref "Z9") (pin "2") (pinfunction "A_2") (pintype "passive"))
    )
    (net (code "20") (name "/HG2C") (class "Default")
      (node (ref "Q9") (pin "1") (pinfunction "G_1") (pintype "passive"))
      (node (ref "R74") (pin "2") (pinfunction "2_2") (pintype "passive"))
      (node (ref "R75") (pin "2") (pinfunction "2_2") (pintype "passive"))
      (node (ref "Z15") (pin "2") (pinfunction "A_2") (pintype "passive"))
    )
    (net (code "21") (name "/HG3") (class "Default")
      (node (ref "Q6") (pin "1") (pinfunction "G_1") (pintype "passive"))
      (node (ref "R20") (pin "2") (pinfunction "2_2") (pintype "passive"))
      (node (ref "R21") (pin "2") (pinfunction "2_2") (pintype "passive"))
      (node (ref "Z5") (pin "2") (pinfunction "A_2") (pintype "passive"))
    )
    (net (code "22") (name "/HG3B") (class "Default")
      (node (ref "Q3") (pin "1") (pinfunction "G_1") (pintype "passive"))
      (node (ref "R62") (pin "2") (pinfunction "2_2") (pintype "passive"))
      (node (ref "R63") (pin "2") (pinfunction "2_2") (pintype "passive"))
      (node (ref "Z11") (pin "2") (pinfunction "A_2") (pintype "passive"))
    )
    (net (code "23") (name "/HG3C") (class "Default")
      (node (ref "Q10") (pin "1") (pinfunction "G_1") (pintype "passive"))
      (node (ref "R80") (pin "2") (pinfunction "2_2") (pintype "passive"))
      (node (ref "R81") (pin "2") (pinfunction "2_2") (pintype "passive"))
      (node (ref "Z17") (pin "2") (pinfunction "A_2") (pintype "passive"))
    )
    (net (code "24") (name "/HI1") (class "Default")
      (node (ref "IC1") (pin "5") (pinfunction "HI_5") (pintype "passive"))
      (node (ref "IC2") (pin "29") (pinfunction "PA8_29") (pintype "passive"))
      (node (ref "R1") (pin "1") (pinfunction "1_1") (pintype "passive"))
    )
    (net (code "25") (name "/HI2") (class "Default")
      (node (ref "IC2") (pin "30") (pinfunction "PA9_30") (pintype "passive"))
      (node (ref "IC3") (pin "5") (pinfunction "HI_5") (pintype "passive"))
      (node (ref "R3") (pin "1") (pinfunction "1_1") (pintype "passive"))
    )
    (net (code "26") (name "/HI3") (class "Default")
      (node (ref "IC2") (pin "31") (pinfunction "PA10_31") (pintype "passive"))
      (node (ref "IC4") (pin "5") (pinfunction "HI_5") (pintype "passive"))
      (node (ref "R5") (pin "1") (pinfunction "1_1") (pintype "passive"))
    )
    (net (code "27") (name "/HO1") (class "Default")
      (node (ref "IC1") (pin "3") (pinfunction "HO_3") (pintype "passive"))
      (node (ref "R49") (pin "1") (pinfunction "1_1") (pintype "passive"))
      (node (ref "R50") (pin "1") (pinfunction "1_1") (pintype "passive"))
      (node (ref "R67") (pin "1") (pinfunction "1_1") (pintype "passive"))
      (node (ref "R68") (pin "1") (pinfunction "1_1") (pintype "passive"))
      (node (ref "R7") (pin "1") (pinfunction "1_1") (pintype "passive"))
      (node (ref "R8") (pin "1") (pinfunction "1_1") (pintype "passive"))
    )
    (net (code "28") (name "/HO2") (class "Default")
      (node (ref "IC3") (pin "3") (pinfunction "HO_3") (pintype "passive"))
      (node (ref "R13") (pin "1") (pinfunction "1_1") (pintype "passive"))
      (node (ref "R14") (pin "1") (pinfunction "1_1") (pintype "passive"))
      (node (ref "R55") (pin "1") (pinfunction "1_1") (pintype "passive"))
      (node (ref "R56") (pin "1") (pinfunction "1_1") (pintype "passive"))
      (node (ref "R73") (pin "1") (pinfunction "1_1") (pintype "passive"))
      (node (ref "R74") (pin "1") (pinfunction "1_1") (pintype "passive"))
    )
    (net (code "29") (name "/HO3") (class "Default")
      (node (ref "IC4") (pin "3") (pinfunction "HO_3") (pintype "passive"))
      (node (ref "R19") (pin "1") (pinfunction "1_1") (pintype "passive"))
      (node (ref "R20") (pin "1") (pinfunction "1_1") (pintype "passive"))
      (node (ref "R61") (pin "1") (pinfunction "1_1") (pintype "passive"))
      (node (ref "R62") (pin "1") (pinfunction "1_1") (pintype "passive"))
      (node (ref "R79") (pin "1") (pinfunction "1_1") (pintype "passive"))
      (node (ref "R80") (pin "1") (pinfunction "1_1") (pintype "passive"))
    )
    (net (code "30") (name "/HS1") (class "Default")
      (node (ref "C46") (pin "2") (pinfunction "2_2") (pintype "passive"))
      (node (ref "C8") (pin "2") (pinfunction "2_2") (pintype "passive"))
      (node (ref "IC1") (pin "4") (pinfunction "HS_4") (pintype "passive"))
      (node (ref "J5") (pin "1") (pinfunction "1_1") (pintype "passive"))
      (node (ref "Q11") (pin "2") (pinfunction "D_2") (pintype "passive"))
      (node (ref "Q13") (pin "2") (pinfunction "D_2") (pintype "passive"))
      (node (ref "Q17") (pin "2") (pinfunction "D_2") (pintype "passive"))
      (node (ref "Q20") (pin "3") (pinfunction "S_3") (pintype "passive"))
      (node (ref "Q4") (pin "3") (pinfunction "S_3") (pintype "passive"))
      (node (ref "Q8") (pin "3") (pinfunction "S_3") (pintype "passive"))
      (node (ref "R51") (pin "1") (pinfunction "1_1") (pintype "passive"))
      (node (ref "R69") (pin "1") (pinfunction "1_1") (pintype "passive"))
      (node (ref "R89") (pin "1") (pinfunction "1_1") (pintype "passive"))
      (node (ref "R9") (pin "1") (pinfunction "1_1") (pintype "passive"))
    )
    (net (code "31") (name "/HS2") (class "Default")
      (node (ref "C10") (pin "2") (pinfunction "2_2") (pintype "passive"))
      (node (ref "C47") (pin "2") (pinfunction "2_2") (pintype "passive"))
      (node (ref "IC3") (pin "4") (pinfunction "HS_4") (pintype "passive"))
      (node (ref "J2") (pin "1") (pinfunction "1_1") (pintype "passive"))
      (node (ref "Q12") (pin "2") (pinfunction "D_2") (pintype "passive"))
      (node (ref "Q14") (pin "2") (pinfunction "D_2") (pintype "passive"))
      (node (ref "Q18") (pin "2") (pinfunction "D_2") (pintype "passive"))
      (node (ref "Q2") (pin "3") (pinfunction "S_3") (pintype "passive"))
      (node (ref "Q5") (pin "3") (pinfunction "S_3") (pintype "passive"))
      (node (ref "Q9") (pin "3") (pinfunction "S_3") (pintype "passive"))
      (node (ref "R15") (pin "1") (pinfunction "1_1") (pintype "passive"))
      (node (ref "R57") (pin "1") (pinfunction "1_1") (pintype "passive"))
      (node (ref "R75") (pin "1") (pinfunction "1_1") (pintype "passive"))
      (node (ref "R90") (pin "1") (pinfunction "1_1") (pintype "passive"))
    )
    (net (code "32") (name "/HS3") (class "Default")
      (node (ref "C12") (pin "2") (pinfunction "2_2") (pintype "passive"))
      (node (ref "C48") (pin "2") (pinfunction "2_2") (pintype "passive"))
      (node (ref "IC4") (pin "4") (pinfunction "HS_4") (pintype "passive"))
      (node (ref "J1") (pin "1") (pinfunction "1_1") (pintype "passive"))
      (node (ref "Q10") (pin "3") (pinfunction "S_3") (pintype "passive"))
      (node (ref "Q15") (pin "2") (pinfunction "D_2") (pintype "passive"))
      (node (ref "Q16") (pin "2") (pinfunction "D_2") (pintype "passive"))
      (node (ref "Q19") (pin "2") (pinfunction "D_2") (pintype "passive"))
      (node (ref "Q3") (pin "3") (pinfunction "S_3") (pintype "passive"))
      (node (ref "Q6") (pin "3") (pinfunction "S_3") (pintype "passive"))
      (node (ref "R21") (pin "1") (pinfunction "1_1") (pintype "passive"))
      (node (ref "R63") (pin "1") (pinfunction "1_1") (pintype "passive"))
      (node (ref "R81") (pin "1") (pinfunction "1_1") (pintype "passive"))
      (node (ref "R91") (pin "1") (pinfunction "1_1") (pintype "passive"))
    )
    (net (code "33") (name "/LG1") (class "Default")
      (node (ref "Q13") (pin "1") (pinfunction "G_1") (pintype "passive"))
      (node (ref "R11") (pin "2") (pinfunction "2_2") (pintype "passive"))
      (node (ref "R12") (pin "2") (pinfunction "2_2") (pintype "passive"))
      (node (ref "Z2") (pin "2") (pinfunction "A_2") (pintype "passive"))
    )
    (net (code "34") (name "/LG1B") (class "Default")
      (node (ref "Q11") (pin "1") (pinfunction "G_1") (pintype "passive"))
      (node (ref "R53") (pin "2") (pinfunction "2_2") (pintype "passive"))
      (node (ref "R54") (pin "2") (pinfunction "2_2") (pintype "passive"))
      (node (ref "Z8") (pin "2") (pinfunction "A_2") (pintype "passive"))
    )
    (net (code "35") (name "/LG1C") (class "Default")
      (node (ref "Q17") (pin "1") (pinfunction "G_1") (pintype "passive"))
      (node (ref "R71") (pin "2") (pinfunction "2_2") (pintype "passive"))
      (node (ref "R72") (pin "2") (pinfunction "2_2") (pintype "passive"))
      (node (ref "Z14") (pin "2") (pinfunction "A_2") (pintype "passive"))
    )
    (net (code "36") (name "/LG2") (class "Default")
      (node (ref "Q14") (pin "1") (pinfunction "G_1") (pintype "passive"))
      (node (ref "R17") (pin "2") (pinfunction "2_2") (pintype "passive"))
      (node (ref "R18") (pin "2") (pinfunction "2_2") (pintype "passive"))
      (node (ref "Z4") (pin "2") (pinfunction "A_2") (pintype "passive"))
    )
    (net (code "37") (name "/LG2B") (class "Default")
      (node (ref "Q12") (pin "1") (pinfunction "G_1") (pintype "passive"))
      (node (ref "R59") (pin "2") (pinfunction "2_2") (pintype "passive"))
      (node (ref "R60") (pin "2") (pinfunction "2_2") (pintype "passive"))
      (node (ref "Z10") (pin "2") (pinfunction "A_2") (pintype "passive"))
    )
    (net (code "38") (name "/LG2C") (class "Default")
      (node (ref "Q18") (pin "1") (pinfunction "G_1") (pintype "passive"))
      (node (ref "R77") (pin "2") (pinfunction "2_2") (pintype "passive"))
      (node (ref "R78") (pin "2") (pinfunction "2_2") (pintype "passive"))
      (node (ref "Z16") (pin "2") (pinfunction "A_2") (pintype "passive"))
    )
    (net (code "39") (name "/LG3") (class "Default")
      (node (ref "Q15") (pin "1") (pinfunction "G_1") (pintype "passive"))
      (node (ref "R23") (pin "2") (pinfunction "2_2") (pintype "passive"))
      (node (ref "R24") (pin "2") (pinfunction "2_2") (pintype "passive"))
      (node (ref "Z6") (pin "2") (pinfunction "A_2") (pintype "passive"))
    )
    (net (code "40") (name "/LG3B") (class "Default")
      (node (ref "Q16") (pin "1") (pinfunction "G_1") (pintype "passive"))
      (node (ref "R65") (pin "2") (pinfunction "2_2") (pintype "passive"))
      (node (ref "R66") (pin "2") (pinfunction "2_2") (pintype "passive"))
      (node (ref "Z12") (pin "2") (pinfunction "A_2") (pintype "passive"))
    )
    (net (code "41") (name "/LG3C") (class "Default")
      (node (ref "Q19") (pin "1") (pinfunction "G_1") (pintype "passive"))
      (node (ref "R83") (pin "2") (pinfunction "2_2") (pintype "passive"))
      (node (ref "R84") (pin "2") (pinfunction "2_2") (pintype "passive"))
      (node (ref "Z18") (pin "2") (pinfunction "A_2") (pintype "passive"))
    )
    (net (code "42") (name "/LI1") (class "Default")
      (node (ref "IC1") (pin "6") (pinfunction "LI_6") (pintype "passive"))
      (node (ref "IC2") (pin "26") (pinfunction "PB13_26") (pintype "passive"))
      (node (ref "R2") (pin "1") (pinfunction "1_1") (pintype "passive"))
    )
    (net (code "43") (name "/LI2") (class "Default")
      (node (ref "IC2") (pin "27") (pinfunction "PB14_27") (pintype "passive"))
      (node (ref "IC3") (pin "6") (pinfunction "LI_6") (pintype "passive"))
      (node (ref "R4") (pin "1") (pinfunction "1_1") (pintype "passive"))
    )
    (net (code "44") (name "/LI3") (class "Default")
      (node (ref "IC2") (pin "28") (pinfunction "PB15_28") (pintype "passive"))
      (node (ref "IC4") (pin "6") (pinfunction "LI_6") (pintype "passive"))
      (node (ref "R6") (pin "1") (pinfunction "1_1") (pintype "passive"))
    )
    (net (code "45") (name "/LO1") (class "Default")
      (node (ref "IC1") (pin "8") (pinfunction "LO_8") (pintype "passive"))
      (node (ref "R10") (pin "1") (pinfunction "1_1") (pintype "passive"))
      (node (ref "R11") (pin "1") (pinfunction "1_1") (pintype "passive"))
      (node (ref "R52") (pin "1") (pinfunction "1_1") (pintype "passive"))
      (node (ref "R53") (pin "1") (pinfunction "1_1") (pintype "passive"))
      (node (ref "R70") (pin "1") (pinfunction "1_1") (pintype "passive"))
      (node (ref "R71") (pin "1") (pinfunction "1_1") (pintype "passive"))
    )
    (net (code "46") (name "/LO2") (class "Default")
      (node (ref "IC3") (pin "8") (pinfunction "LO_8") (pintype "passive"))
      (node (ref "R16") (pin "1") (pinfunction "1_1") (pintype "passive"))
      (node (ref "R17") (pin "1") (pinfunction "1_1") (pintype "passive"))
      (node (ref "R58") (pin "1") (pinfunction "1_1") (pintype "passive"))
      (node (ref "R59") (pin "1") (pinfunction "1_1") (pintype "passive"))
      (node (ref "R76") (pin "1") (pinfunction "1_1") (pintype "passive"))
      (node (ref "R77") (pin "1") (pinfunction "1_1") (pintype "passive"))
    )
    (net (code "47") (name "/LO3") (class "Default")
      (node (ref "IC4") (pin "8") (pinfunction "LO_8") (pintype "passive"))
      (node (ref "R22") (pin "1") (pinfunction "1_1") (pintype "passive"))
      (node (ref "R23") (pin "1") (pinfunction "1_1") (pintype "passive"))
      (node (ref "R64") (pin "1") (pinfunction "1_1") (pintype "passive"))
      (node (ref "R65") (pin "1") (pinfunction "1_1") (pintype "passive"))
      (node (ref "R82") (pin "1") (pinfunction "1_1") (pintype "passive"))
      (node (ref "R83") (pin "1") (pinfunction "1_1") (pintype "passive"))
    )
    (net (code "48") (name "/MOD1") (class "Default")
      (node (ref "IC2") (pin "41") (pinfunction "PB5_41") (pintype "passive"))
      (node (ref "J12") (pin "2") (pinfunction "9_2") (pintype "passive"))
      (node (ref "R88") (pin "2") (pinfunction "2_2") (pintype "passive"))
    )
    (net (code "49") (name "/NRST") (class "Default")
      (node (ref "C22") (pin "2") (pinfunction "2_2") (pintype "passive"))
      (node (ref "IC2") (pin "7") (pinfunction "NRST_7") (pintype "passive"))
      (node (ref "R26") (pin "2") (pinfunction "2_2") (pintype "passive"))
      (node (ref "S1") (pin "1") (pinfunction "COM_1") (pintype "passive"))
    )
    (net (code "50") (name "/PA15") (class "Default")
      (node (ref "IC2") (pin "38") (pinfunction "PA15_38") (pintype "passive"))
      (node (ref "J14") (pin "3") (pinfunction "3_3") (pintype "passive"))
    )
    (net (code "51") (name "/PB2") (class "Default")
      (node (ref "IC2") (pin "20") (pinfunction "PB2_20") (pintype "passive"))
      (node (ref "J16") (pin "1") (pinfunction "1_1") (pintype "passive"))
    )
    (net (code "52") (name "/PB3") (class "Default")
      (node (ref "IC2") (pin "39") (pinfunction "PB3_39") (pintype "passive"))
      (node (ref "J14") (pin "2") (pinfunction "2_2") (pintype "passive"))
    )
    (net (code "53") (name "/PB4") (class "Default")
      (node (ref "IC2") (pin "40") (pinfunction "PB4_40") (pintype "passive"))
      (node (ref "J14") (pin "1") (pinfunction "1_1") (pintype "passive"))
    )
    (net (code "54") (name "/PB8") (class "Default")
      (node (ref "IC2") (pin "45") (pinfunction "PB8_45") (pintype "passive"))
      (node (ref "J13") (pin "2") (pinfunction "2_2") (pintype "passive"))
    )
    (net (code "55") (name "/PB9") (class "Default")
      (node (ref "IC2") (pin "46") (pinfunction "PB9_46") (pintype "passive"))
      (node (ref "J13") (pin "3") (pinfunction "3_3") (pintype "passive"))
    )
    (net (code "56") (name "/PB10") (class "Default")
      (node (ref "IC2") (pin "21") (pinfunction "PB10_21") (pintype "passive"))
      (node (ref "J16") (pin "2") (pinfunction "2_2") (pintype "passive"))
    )
    (net (code "57") (name "/PB11") (class "Default")
      (node (ref "IC2") (pin "22") (pinfunction "PB11_22") (pintype "passive"))
      (node (ref "J16") (pin "3") (pinfunction "3_3") (pintype "passive"))
    )
    (net (code "58") (name "/PB12") (class "Default")
      (node (ref "IC2") (pin "25") (pinfunction "PB12_25") (pintype "passive"))
      (node (ref "IC8") (pin "1") (pinfunction "OUT_1") (pintype "output"))
    )
    (net (code "59") (name "/PC13") (class "Default")
      (node (ref "IC2") (pin "2") (pinfunction "PC13-TAMPER-RT_C_2") (pintype "passive"))
      (node (ref "J15") (pin "3") (pinfunction "3_3") (pintype "passive"))
    )
    (net (code "60") (name "/PC14") (class "Default")
      (node (ref "IC2") (pin "3") (pinfunction "PC14-OSC32_IN_3") (pintype "passive"))
      (node (ref "J15") (pin "2") (pinfunction "2_2") (pintype "passive"))
    )
    (net (code "61") (name "/PC15") (class "Default")
      (node (ref "IC2") (pin "4") (pinfunction "PC15-OSC32_OUT_4") (pintype "passive"))
      (node (ref "J15") (pin "1") (pinfunction "1_1") (pintype "passive"))
    )
    (net (code "62") (name "/RX1") (class "Default")
      (node (ref "IC2") (pin "43") (pinfunction "PB7_43") (pintype "passive"))
      (node (ref "jst3") (pin "3") (pinfunction "3_3") (pintype "passive"))
    )
    (net (code "63") (name "/S") (class "Default")
      (node (ref "C49") (pin "1") (pinfunction "1_1") (pintype "passive"))
      (node (ref "IC2") (pin "18") (pinfunction "PB0_18") (pintype "passive"))
      (node (ref "IC8") (pin "4") (pinfunction "IN-_4") (pintype "input"))
      (node (ref "R42") (pin "2") (pinfunction "2_2") (pintype "passive"))
      (node (ref "R48") (pin "2") (pinfunction "2_2") (pintype "passive"))
    )
    (net (code "64") (name "/SPEED_M") (class "Default")
      (node (ref "IC2") (pin "14") (pinfunction "PA4_14") (pintype "passive"))
      (node (ref "J9") (pin "1") (pinfunction "2_1") (pintype "passive"))
      (node (ref "R46") (pin "2") (pinfunction "2_2") (pintype "passive"))
    )
    (net (code "65") (name "/SWCLK") (class "Default")
      (node (ref "IC2") (pin "37") (pinfunction "PA14_37") (pintype "passive"))
      (node (ref "jst2") (pin "2") (pinfunction "2_2") (pintype "passive"))
    )
    (net (code "66") (name "/SWDIO") (class "Default")
      (node (ref "IC2") (pin "34") (pinfunction "PA13_34") (pintype "passive"))
      (node (ref "jst2") (pin "4") (pinfunction "4_4") (pintype "passive"))
    )
    (net (code "67") (name "/TEMP1") (class "Default")
      (node (ref "IC2") (pin "17") (pinfunction "PA7_17") (pintype "passive"))
      (node (ref "R40") (pin "1") (pinfunction "1_1") (pintype "passive"))
      (node (ref "jst4") (pin "2") (pinfunction "2_2") (pintype "passive"))
    )
    (net (code "68") (name "/TEMP2") (class "Default")
      (node (ref "IC2") (pin "16") (pinfunction "PA6_16") (pintype "passive"))
      (node (ref "R39") (pin "1") (pinfunction "1_1") (pintype "passive"))
      (node (ref "jst5") (pin "2") (pinfunction "2_2") (pintype "passive"))
    )
    (net (code "69") (name "/TX1") (class "Default")
      (node (ref "IC2") (pin "42") (pinfunction "PB6_42") (pintype "passive"))
      (node (ref "jst3") (pin "2") (pinfunction "2_2") (pintype "passive"))
    )
    (net (code "70") (name "/VBAT") (class "Default")
      (node (ref "C1") (pin "1") (pinfunction "1_1") (pintype "passive"))
      (node (ref "C13") (pin "1") (pintype "passive"))
      (node (ref "C14") (pin "1") (pintype "passive"))
      (node (ref "C19") (pin "1") (pinfunction "1_1") (pintype "passive"))
      (node (ref "C2") (pin "1") (pinfunction "1_1") (pintype "passive"))
      (node (ref "C3") (pin "1") (pinfunction "1_1") (pintype "passive"))
      (node (ref "C30") (pin "1") (pintype "passive"))
      (node (ref "C31") (pin "1") (pintype "passive"))
      (node (ref "C4") (pin "1") (pinfunction "1_1") (pintype "passive"))
      (node (ref "C5") (pin "1") (pinfunction "1_1") (pintype "passive"))
      (node (ref "C50") (pin "1") (pinfunction "1_1") (pintype "passive"))
      (node (ref "C52") (pin "1") (pinfunction "1_1") (pintype "passive"))
      (node (ref "C53") (pin "1") (pinfunction "1_1") (pintype "passive"))
      (node (ref "IC6") (pin "2") (pinfunction "VIN_2") (pintype "passive"))
      (node (ref "IC6") (pin "3") (pinfunction "EN/UVLO_3") (pintype "passive"))
      (node (ref "J7") (pin "1") (pinfunction "1_1") (pintype "passive"))
      (node (ref "Q10") (pin "2") (pinfunction "D_2") (pintype "passive"))
      (node (ref "Q2") (pin "2") (pinfunction "D_2") (pintype "passive"))
      (node (ref "Q20") (pin "2") (pinfunction "D_2") (pintype "passive"))
      (node (ref "Q3") (pin "2") (pinfunction "D_2") (pintype "passive"))
      (node (ref "Q4") (pin "2") (pinfunction "D_2") (pintype "passive"))
      (node (ref "Q5") (pin "2") (pinfunction "D_2") (pintype "passive"))
      (node (ref "Q6") (pin "2") (pinfunction "D_2") (pintype "passive"))
      (node (ref "Q8") (pin "2") (pinfunction "D_2") (pintype "passive"))
      (node (ref "Q9") (pin "2") (pinfunction "D_2") (pintype "passive"))
      (node (ref "R43") (pin "2") (pinfunction "2_2") (pintype "passive"))
    )
    (net (code "71") (name "/osc1") (class "Default")
      (node (ref "C24") (pin "2") (pinfunction "2_2") (pintype "passive"))
      (node (ref "IC2") (pin "5") (pinfunction "PD0-OSC_IN_5") (pintype "passive"))
      (node (ref "X1") (pin "2") (pinfunction "2_2") (pintype "passive"))
    )
    (net (code "72") (name "/osc2") (class "Default")
      (node (ref "C23") (pin "2") (pinfunction "2_2") (pintype "passive"))
      (node (ref "IC2") (pin "6") (pinfunction "PD1-OSC_OUT_6") (pintype "passive"))
      (node (ref "X1") (pin "1") (pinfunction "1_1") (pintype "passive"))
    )
    (net (code "73") (name "/speed") (class "Default")
      (node (ref "C6") (pin "1") (pinfunction "1_1") (pintype "passive"))
      (node (ref "IC2") (pin "15") (pinfunction "PA5_15") (pintype "passive"))
      (node (ref "R85") (pin "2") (pinfunction "2_2") (pintype "passive"))
      (node (ref "R86") (pin "2") (pinfunction "2_2") (pintype "passive"))
    )
    (net (code "74") (name "/voltage") (class "Default")
      (node (ref "IC2") (pin "19") (pinfunction "PB1_19") (pintype "passive"))
      (node (ref "R43") (pin "1") (pinfunction "1_1") (pintype "passive"))
      (node (ref "R44") (pin "2") (pinfunction "2_2") (pintype "passive"))
    )
    (net (code "75") (name "GND") (class "Default")
      (node (ref "C1") (pin "2") (pinfunction "2_2") (pintype "passive"))
      (node (ref "C11") (pin "1") (pinfunction "1_1") (pintype "passive"))
      (node (ref "C13") (pin "2") (pintype "passive"))
      (node (ref "C14") (pin "2") (pintype "passive"))
      (node (ref "C17") (pin "2") (pinfunction "2_2") (pintype "passive"))
      (node (ref "C18") (pin "2") (pinfunction "2_2") (pintype "passive"))
      (node (ref "C19") (pin "2") (pinfunction "2_2") (pintype "passive"))
      (node (ref "C2") (pin "2") (pinfunction "2_2") (pintype "passive"))
      (node (ref "C21") (pin "2") (pinfunction "2_2") (pintype "passive"))
      (node (ref "C22") (pin "1") (pinfunction "1_1") (pintype "passive"))
      (node (ref "C23") (pin "1") (pinfunction "1_1") (pintype "passive"))
      (node (ref "C24") (pin "1") (pinfunction "1_1") (pintype "passive"))
      (node (ref "C25") (pin "1") (pinfunction "1_1") (pintype "passive"))
      (node (ref "C26") (pin "1") (pinfunction "1_1") (pintype "passive"))
      (node (ref "C27") (pin "1") (pinfunction "1_1") (pintype "passive"))
      (node (ref "C28") (pin "2") (pinfunction "2_2") (pintype "passive"))
      (node (ref "C29") (pin "2") (pinfunction "2_2") (pintype "passive"))
      (node (ref "C3") (pin "2") (pinfunction "2_2") (pintype "passive"))
      (node (ref "C30") (pin "2") (pintype "passive"))
      (node (ref "C31") (pin "2") (pintype "passive"))
      (node (ref "C33") (pin "1") (pinfunction "1_1") (pintype "passive"))
      (node (ref "C34") (pin "1") (pinfunction "1_1") (pintype "passive"))
      (node (ref "C35") (pin "1") (pinfunction "1_1") (pintype "passive"))
      (node (ref "C36") (pin "2") (pinfunction "2_2") (pintype "passive"))
      (node (ref "C37") (pin "2") (pinfunction "2_2") (pintype "passive"))
      (node (ref "C38") (pin "1") (pinfunction "1_1") (pintype "passive"))
      (node (ref "C39") (pin "2") (pinfunction "2_2") (pintype "passive"))
      (node (ref "C4") (pin "2") (pinfunction "2_2") (pintype "passive"))
      (node (ref "C40") (pin "2") (pinfunction "2_2") (pintype "passive"))
      (node (ref "C41") (pin "2") (pinfunction "2_2") (pintype "passive"))
      (node (ref "C42") (pin "1") (pinfunction "1_1") (pintype "passive"))
      (node (ref "C43") (pin "2") (pinfunction "2_2") (pintype "passive"))
      (node (ref "C44") (pin "1") (pinfunction "1_1") (pintype "passive"))
      (node (ref "C45") (pin "2") (pinfunction "2_2") (pintype "passive"))
      (node (ref "C49") (pin "2") (pinfunction "2_2") (pintype "passive"))
      (node (ref "C5") (pin "2") (pinfunction "2_2") (pintype "passive"))
      (node (ref "C50") (pin "2") (pinfunction "2_2") (pintype "passive"))
      (node (ref "C51") (pin "1") (pintype "passive"))
      (node (ref "C52") (pin "2") (pinfunction "2_2") (pintype "passive"))
      (node (ref "C53") (pin "2") (pinfunction "2_2") (pintype "passive"))
      (node (ref "C54") (pin "1") (pintype "passive"))
      (node (ref "C55") (pin "1") (pintype "passive"))
      (node (ref "C6") (pin "2") (pinfunction "2_2") (pintype "passive"))
      (node (ref "C7") (pin "1") (pinfunction "1_1") (pintype "passive"))
      (node (ref "C9") (pin "1") (pinfunction "1_1") (pintype "passive"))
      (node (ref "IC1") (pin "7") (pinfunction "VSS_7") (pintype "passive"))
      (node (ref "IC2") (pin "23") (pinfunction "VSS_1_23") (pintype "passive"))
      (node (ref "IC2") (pin "35") (pinfunction "VSS_2_35") (pintype "passive"))
      (node (ref "IC2") (pin "47") (pinfunction "VSS_3_47") (pintype "passive"))
      (node (ref "IC2") (pin "8") (pinfunction "VSSA_8") (pintype "passive"))
      (node (ref "IC3") (pin "7") (pinfunction "VSS_7") (pintype "passive"))
      (node (ref "IC4") (pin "7") (pinfunction "VSS_7") (pintype "passive"))
      (node (ref "IC5") (pin "2") (pinfunction "GND_2") (pintype "passive"))
      (node (ref "IC5") (pin "4") (pinfunction "IP+_4") (pintype "passive"))
      (node (ref "IC5") (pin "5") (pinfunction "IP-_5") (pintype "passive"))
      (node (ref "IC6") (pin "1") (pinfunction "GND_1") (pintype "passive"))
      (node (ref "IC6") (pin "9") (pinfunction "EP_9") (pintype "passive"))
      (node (ref "IC7") (pin "2") (pinfunction "VSS_2") (pintype "passive"))
      (node (ref "IC8") (pin "2") (pinfunction "VSS_2") (pintype "power_in"))
      (node (ref "IC9") (pin "7") (pinfunction "GND_7") (pintype "passive"))
      (node (ref "J10") (pin "2") (pinfunction "9_2") (pintype "passive"))
      (node (ref "J11") (pin "2") (pinfunction "9_2") (pintype "passive"))
      (node (ref "J12") (pin "1") (pinfunction "2_1") (pintype "passive"))
      (node (ref "J13") (pin "1") (pinfunction "1_1") (pintype "passive"))
      (node (ref "J3") (pin "4") (pinfunction "4_4") (pintype "passive"))
      (node (ref "J4") (pin "1") (pinfunction "2_1") (pintype "passive"))
      (node (ref "J6") (pin "1") (pinfunction "1_1") (pintype "passive"))
      (node (ref "J9") (pin "2") (pinfunction "9_2") (pintype "passive"))
      (node (ref "LED1") (pin "1") (pinfunction "K_1") (pintype "passive"))
      (node (ref "Q11") (pin "3") (pinfunction "S_3") (pintype "passive"))
      (node (ref "Q12") (pin "3") (pinfunction "S_3") (pintype "passive"))
      (node (ref "Q13") (pin "3") (pinfunction "S_3") (pintype "passive"))
      (node (ref "Q14") (pin "3") (pinfunction "S_3") (pintype "passive"))
      (node (ref "Q15") (pin "3") (pinfunction "S_3") (pintype "passive"))
      (node (ref "Q16") (pin "3") (pinfunction "S_3") (pintype "passive"))
      (node (ref "Q17") (pin "3") (pinfunction "S_3") (pintype "passive"))
      (node (ref "Q18") (pin "3") (pinfunction "S_3") (pintype "passive"))
      (node (ref "Q19") (pin "3") (pinfunction "S_3") (pintype "passive"))
      (node (ref "Q7") (pin "3") (pinfunction "E_3") (pintype "passive"))
      (node (ref "R1") (pin "2") (pinfunction "2_2") (pintype "passive"))
      (node (ref "R12") (pin "1") (pinfunction "1_1") (pintype "passive"))
      (node (ref "R18") (pin "1") (pinfunction "1_1") (pintype "passive"))
      (node (ref "R2") (pin "2") (pinfunction "2_2") (pintype "passive"))
      (node (ref "R24") (pin "1") (pinfunction "1_1") (pintype "passive"))
      (node (ref "R3") (pin "2") (pinfunction "2_2") (pintype "passive"))
      (node (ref "R35") (pin "2") (pinfunction "2_2") (pintype "passive"))
      (node (ref "R36") (pin "2") (pinfunction "2_2") (pintype "passive"))
      (node (ref "R37") (pin "1") (pinfunction "1_1") (pintype "passive"))
      (node (ref "R4") (pin "2") (pinfunction "2_2") (pintype "passive"))
      (node (ref "R44") (pin "1") (pinfunction "1_1") (pintype "passive"))
      (node (ref "R48") (pin "1") (pinfunction "1_1") (pintype "passive"))
      (node (ref "R5") (pin "2") (pinfunction "2_2") (pintype "passive"))
      (node (ref "R54") (pin "1") (pinfunction "1_1") (pintype "passive"))
      (node (ref "R6") (pin "2") (pinfunction "2_2") (pintype "passive"))
      (node (ref "R60") (pin "1") (pinfunction "1_1") (pintype "passive"))
      (node (ref "R66") (pin "1") (pinfunction "1_1") (pintype "passive"))
      (node (ref "R72") (pin "1") (pinfunction "1_1") (pintype "passive"))
      (node (ref "R78") (pin "1") (pinfunction "1_1") (pintype "passive"))
      (node (ref "R84") (pin "1") (pinfunction "1_1") (pintype "passive"))
      (node (ref "R86") (pin "1") (pinfunction "1_1") (pintype "passive"))
      (node (ref "R87") (pin "2") (pinfunction "2_2") (pintype "passive"))
      (node (ref "S1") (pin "2") (pinfunction "NO_2") (pintype "passive"))
      (node (ref "U1") (pin "1") (pinfunction "GND_1") (pintype "passive"))
      (node (ref "U2") (pin "3") (pinfunction "GND_3") (pintype "passive"))
      (node (ref "VR1") (pin "1") (pinfunction "CCW_1") (pintype "passive"))
      (node (ref "jst1") (pin "1") (pinfunction "1_1") (pintype "passive"))
      (node (ref "jst2") (pin "3") (pinfunction "3_3") (pintype "passive"))
      (node (ref "jst3") (pin "1") (pinfunction "1_1") (pintype "passive"))
      (node (ref "jst4") (pin "3") (pinfunction "3_3") (pintype "passive"))
      (node (ref "jst5") (pin "3") (pinfunction "3_3") (pintype "passive"))
    )
    (net (code "76") (name "Net-(C15-Pad2)") (class "Default")
      (node (ref "C15") (pin "2") (pinfunction "2_2") (pintype "passive"))
      (node (ref "C20") (pin "1") (pinfunction "1_1") (pintype "passive"))
      (node (ref "R25") (pin "1") (pinfunction "1_1") (pintype "passive"))
    )
    (net (code "77") (name "Net-(C51-Pad2)") (class "Default")
      (node (ref "C51") (pin "2") (pintype "passive"))
      (node (ref "R89") (pin "2") (pinfunction "2_2") (pintype "passive"))
    )
    (net (code "78") (name "Net-(C54-Pad2)") (class "Default")
      (node (ref "C54") (pin "2") (pintype "passive"))
      (node (ref "R90") (pin "2") (pinfunction "2_2") (pintype "passive"))
    )
    (net (code "79") (name "Net-(C55-Pad2)") (class "Default")
      (node (ref "C55") (pin "2") (pintype "passive"))
      (node (ref "R91") (pin "2") (pinfunction "2_2") (pintype "passive"))
    )
    (net (code "80") (name "Net-(IC1-HB)") (class "Default")
      (node (ref "C46") (pin "1") (pinfunction "1_1") (pintype "passive"))
      (node (ref "C8") (pin "1") (pinfunction "1_1") (pintype "passive"))
      (node (ref "IC1") (pin "2") (pinfunction "HB_2") (pintype "passive"))
    )
    (net (code "81") (name "Net-(IC2-BOOT0)") (class "Default")
      (node (ref "IC2") (pin "44") (pinfunction "BOOT0_44") (pintype "passive"))
      (node (ref "R87") (pin "1") (pinfunction "1_1") (pintype "passive"))
    )
    (net (code "82") (name "Net-(IC3-HB)") (class "Default")
      (node (ref "C10") (pin "1") (pinfunction "1_1") (pintype "passive"))
      (node (ref "C47") (pin "1") (pinfunction "1_1") (pintype "passive"))
      (node (ref "IC3") (pin "2") (pinfunction "HB_2") (pintype "passive"))
    )
    (net (code "83") (name "Net-(IC4-HB)") (class "Default")
      (node (ref "C12") (pin "1") (pinfunction "1_1") (pintype "passive"))
      (node (ref "C48") (pin "1") (pinfunction "1_1") (pintype "passive"))
      (node (ref "IC4") (pin "2") (pinfunction "HB_2") (pintype "passive"))
    )
    (net (code "84") (name "Net-(IC5-VCC)") (class "Default")
      (node (ref "IC5") (pin "1") (pinfunction "VCC_1") (pintype "passive"))
      (node (ref "R42") (pin "1") (pinfunction "1_1") (pintype "passive"))
    )
    (net (code "85") (name "Net-(IC6-BST)") (class "Default")
      (node (ref "C16") (pin "2") (pinfunction "2_2") (pintype "passive"))
      (node (ref "IC6") (pin "7") (pinfunction "BST_7") (pintype "passive"))
    )
    (net (code "86") (name "Net-(IC6-FB)") (class "Default")
      (node (ref "C20") (pin "2") (pinfunction "2_2") (pintype "passive"))
      (node (ref "IC6") (pin "5") (pinfunction "FB_5") (pintype "passive"))
      (node (ref "R34") (pin "2") (pinfunction "2_2") (pintype "passive"))
      (node (ref "R36") (pin "1") (pinfunction "1_1") (pintype "passive"))
    )
    (net (code "87") (name "Net-(IC6-RON)") (class "Default")
      (node (ref "IC6") (pin "4") (pinfunction "RON_4") (pintype "passive"))
      (node (ref "R35") (pin "1") (pinfunction "1_1") (pintype "passive"))
    )
    (net (code "88") (name "Net-(IC6-SW)") (class "Default")
      (node (ref "C16") (pin "1") (pinfunction "1_1") (pintype "passive"))
      (node (ref "IC6") (pin "8") (pinfunction "SW_8") (pintype "passive"))
      (node (ref "L1") (pin "1") (pinfunction "1_1") (pintype "passive"))
      (node (ref "R25") (pin "2") (pinfunction "2_2") (pintype "passive"))
    )
    (net (code "89") (name "Net-(IC7-CANH)") (class "Default")
      (node (ref "IC7") (pin "7") (pinfunction "CANH_7") (pintype "passive"))
      (node (ref "J8") (pin "2") (pinfunction "9_2") (pintype "passive"))
      (node (ref "R38") (pin "1") (pinfunction "1_1") (pintype "passive"))
    )
    (net (code "90") (name "Net-(IC7-CANL)") (class "Default")
      (node (ref "IC7") (pin "6") (pinfunction "CANL_6") (pintype "passive"))
      (node (ref "J8") (pin "1") (pinfunction "2_1") (pintype "passive"))
      (node (ref "R38") (pin "2") (pinfunction "2_2") (pintype "passive"))
    )
    (net (code "91") (name "Net-(IC7-RS)") (class "Default")
      (node (ref "IC7") (pin "8") (pinfunction "RS_8") (pintype "passive"))
      (node (ref "R37") (pin "2") (pinfunction "2_2") (pintype "passive"))
    )
    (net (code "92") (name "Net-(IC8-IN+)") (class "Default")
      (node (ref "IC8") (pin "3") (pinfunction "IN+_3") (pintype "input"))
      (node (ref "VR1") (pin "2") (pinfunction "WIPER_2") (pintype "passive"))
    )
    (net (code "93") (name "Net-(J3-Pad1)") (class "Default")
      (node (ref "J3") (pin "1") (pinfunction "1_1") (pintype "passive"))
      (node (ref "R32") (pin "1") (pinfunction "1_1") (pintype "passive"))
    )
    (net (code "94") (name "Net-(J3-Pad2)") (class "Default")
      (node (ref "J3") (pin "2") (pinfunction "2_2") (pintype "passive"))
      (node (ref "R31") (pin "1") (pinfunction "1_1") (pintype "passive"))
    )
    (net (code "95") (name "Net-(J3-Pad3)") (class "Default")
      (node (ref "J3") (pin "3") (pinfunction "3_3") (pintype "passive"))
      (node (ref "R30") (pin "1") (pinfunction "1_1") (pintype "passive"))
    )
    (net (code "96") (name "Net-(LED1-A)") (class "Default")
      (node (ref "LED1") (pin "2") (pinfunction "A_2") (pintype "passive"))
      (node (ref "R41") (pin "1") (pinfunction "1_1") (pintype "passive"))
    )
    (net (code "97") (name "Net-(Q7-B)") (class "Default")
      (node (ref "Q7") (pin "2") (pinfunction "B_2") (pintype "passive"))
      (node (ref "R47") (pin "1") (pinfunction "1_1") (pintype "passive"))
    )
    (net (code "98") (name "Net-(Q7-C)") (class "Default")
      (node (ref "Q7") (pin "1") (pinfunction "C_1") (pintype "passive"))
      (node (ref "R45") (pin "1") (pinfunction "1_1") (pintype "passive"))
      (node (ref "R46") (pin "1") (pinfunction "1_1") (pintype "passive"))
    )
    (net (code "99") (name "Net-(R85-Pad1)") (class "Default")
      (node (ref "R85") (pin "1") (pinfunction "1_1") (pintype "passive"))
      (node (ref "jst1") (pin "2") (pinfunction "2_2") (pintype "passive"))
    )
    (net (code "100") (name "Net-(Z1-K)") (class "Default")
      (node (ref "R7") (pin "2") (pinfunction "2_2") (pintype "passive"))
      (node (ref "Z1") (pin "1") (pinfunction "K_1") (pintype "passive"))
    )
    (net (code "101") (name "Net-(Z2-K)") (class "Default")
      (node (ref "R10") (pin "2") (pinfunction "2_2") (pintype "passive"))
      (node (ref "Z2") (pin "1") (pinfunction "K_1") (pintype "passive"))
    )
    (net (code "102") (name "Net-(Z3-K)") (class "Default")
      (node (ref "R13") (pin "2") (pinfunction "2_2") (pintype "passive"))
      (node (ref "Z3") (pin "1") (pinfunction "K_1") (pintype "passive"))
    )
    (net (code "103") (name "Net-(Z4-K)") (class "Default")
      (node (ref "R16") (pin "2") (pinfunction "2_2") (pintype "passive"))
      (node (ref "Z4") (pin "1") (pinfunction "K_1") (pintype "passive"))
    )
    (net (code "104") (name "Net-(Z5-K)") (class "Default")
      (node (ref "R19") (pin "2") (pinfunction "2_2") (pintype "passive"))
      (node (ref "Z5") (pin "1") (pinfunction "K_1") (pintype "passive"))
    )
    (net (code "105") (name "Net-(Z6-K)") (class "Default")
      (node (ref "R22") (pin "2") (pinfunction "2_2") (pintype "passive"))
      (node (ref "Z6") (pin "1") (pinfunction "K_1") (pintype "passive"))
    )
    (net (code "106") (name "Net-(Z7-K)") (class "Default")
      (node (ref "R49") (pin "2") (pinfunction "2_2") (pintype "passive"))
      (node (ref "Z7") (pin "1") (pinfunction "K_1") (pintype "passive"))
    )
    (net (code "107") (name "Net-(Z8-K)") (class "Default")
      (node (ref "R52") (pin "2") (pinfunction "2_2") (pintype "passive"))
      (node (ref "Z8") (pin "1") (pinfunction "K_1") (pintype "passive"))
    )
    (net (code "108") (name "Net-(Z9-K)") (class "Default")
      (node (ref "R55") (pin "2") (pinfunction "2_2") (pintype "passive"))
      (node (ref "Z9") (pin "1") (pinfunction "K_1") (pintype "passive"))
    )
    (net (code "109") (name "Net-(Z10-K)") (class "Default")
      (node (ref "R58") (pin "2") (pinfunction "2_2") (pintype "passive"))
      (node (ref "Z10") (pin "1") (pinfunction "K_1") (pintype "passive"))
    )
    (net (code "110") (name "Net-(Z11-K)") (class "Default")
      (node (ref "R61") (pin "2") (pinfunction "2_2") (pintype "passive"))
      (node (ref "Z11") (pin "1") (pinfunction "K_1") (pintype "passive"))
    )
    (net (code "111") (name "Net-(Z12-K)") (class "Default")
      (node (ref "R64") (pin "2") (pinfunction "2_2") (pintype "passive"))
      (node (ref "Z12") (pin "1") (pinfunction "K_1") (pintype "passive"))
    )
    (net (code "112") (name "Net-(Z13-K)") (class "Default")
      (node (ref "R67") (pin "2") (pinfunction "2_2") (pintype "passive"))
      (node (ref "Z13") (pin "1") (pinfunction "K_1") (pintype "passive"))
    )
    (net (code "113") (name "Net-(Z14-K)") (class "Default")
      (node (ref "R70") (pin "2") (pinfunction "2_2") (pintype "passive"))
      (node (ref "Z14") (pin "1") (pinfunction "K_1") (pintype "passive"))
    )
    (net (code "114") (name "Net-(Z15-K)") (class "Default")
      (node (ref "R73") (pin "2") (pinfunction "2_2") (pintype "passive"))
      (node (ref "Z15") (pin "1") (pinfunction "K_1") (pintype "passive"))
    )
    (net (code "115") (name "Net-(Z16-K)") (class "Default")
      (node (ref "R76") (pin "2") (pinfunction "2_2") (pintype "passive"))
      (node (ref "Z16") (pin "1") (pinfunction "K_1") (pintype "passive"))
    )
    (net (code "116") (name "Net-(Z17-K)") (class "Default")
      (node (ref "R79") (pin "2") (pinfunction "2_2") (pintype "passive"))
      (node (ref "Z17") (pin "1") (pinfunction "K_1") (pintype "passive"))
    )
    (net (code "117") (name "Net-(Z18-K)") (class "Default")
      (node (ref "R82") (pin "2") (pinfunction "2_2") (pintype "passive"))
      (node (ref "Z18") (pin "1") (pinfunction "K_1") (pintype "passive"))
    )
    (net (code "118") (name "unconnected-(IC6-PGOOD-Pad6)") (class "Default")
      (node (ref "IC6") (pin "6") (pinfunction "PGOOD_6") (pintype "passive"))
    )
    (net (code "119") (name "unconnected-(IC7-VREF-Pad5)") (class "Default")
      (node (ref "IC7") (pin "5") (pinfunction "VREF_5") (pintype "passive"))
    )
    (net (code "120") (name "unconnected-(IC9-4A-Pad9)") (class "Default")
      (node (ref "IC9") (pin "9") (pinfunction "4A_9") (pintype "passive"))
    )
    (net (code "121") (name "unconnected-(IC9-4Y-Pad8)") (class "Default")
      (node (ref "IC9") (pin "8") (pinfunction "4Y_8") (pintype "passive"))
    )
    (net (code "122") (name "unconnected-(IC9-5A-Pad11)") (class "Default")
      (node (ref "IC9") (pin "11") (pinfunction "5A_11") (pintype "passive"))
    )
    (net (code "123") (name "unconnected-(IC9-5Y-Pad10)") (class "Default")
      (node (ref "IC9") (pin "10") (pinfunction "5Y_10") (pintype "passive"))
    )
    (net (code "124") (name "unconnected-(IC9-6A-Pad13)") (class "Default")
      (node (ref "IC9") (pin "13") (pinfunction "6A_13") (pintype "passive"))
    )
    (net (code "125") (name "unconnected-(IC9-6Y-Pad12)") (class "Default")
      (node (ref "IC9") (pin "12") (pinfunction "6Y_12") (pintype "passive"))
    )
  )
)
